# EEZ_DIB_DCP405_r2B11.net
KiCad netlist of a schematic drawn in EAGLE
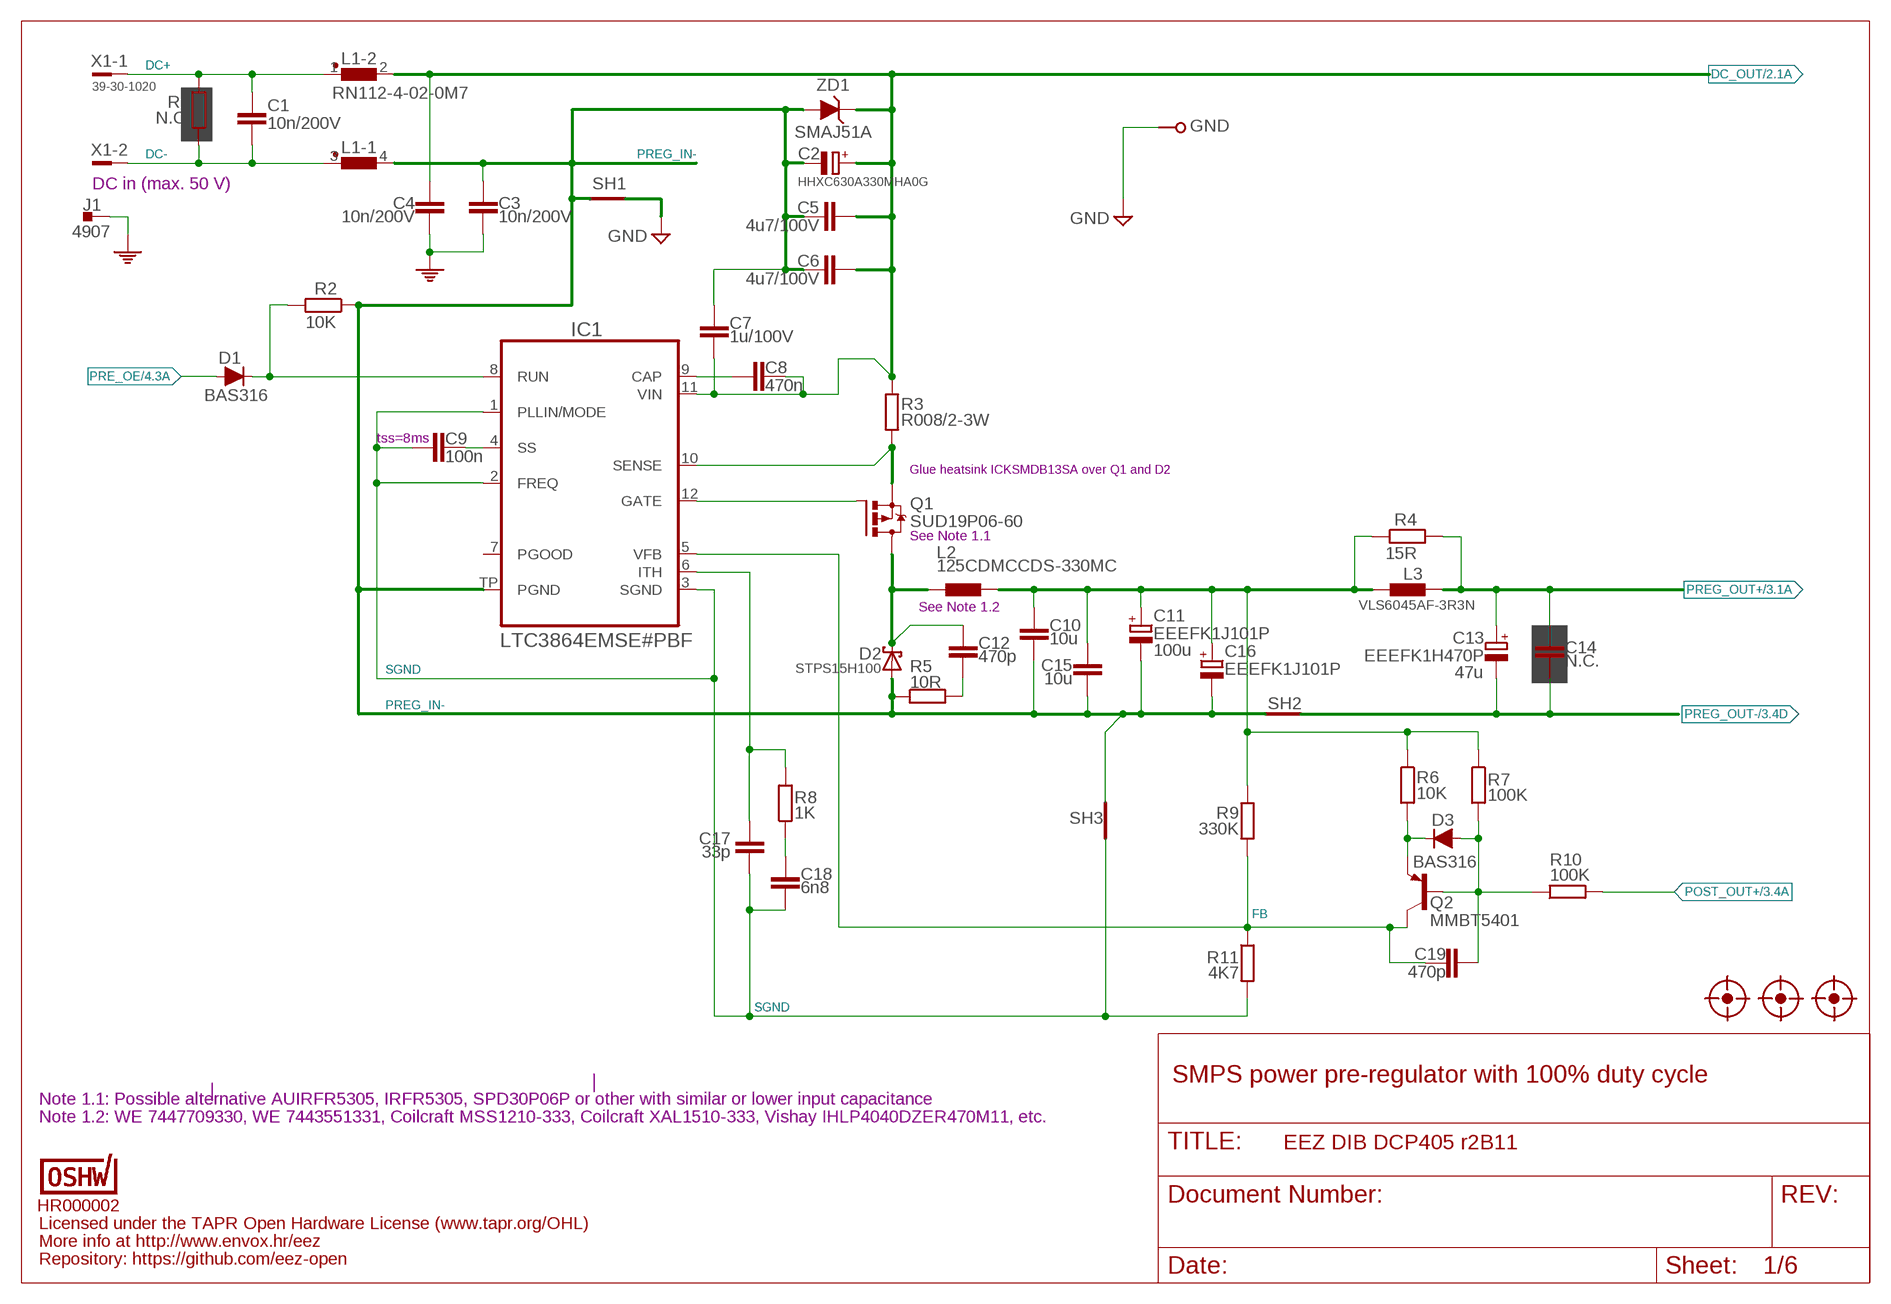
[diagram p0: schematic, sheet 1]
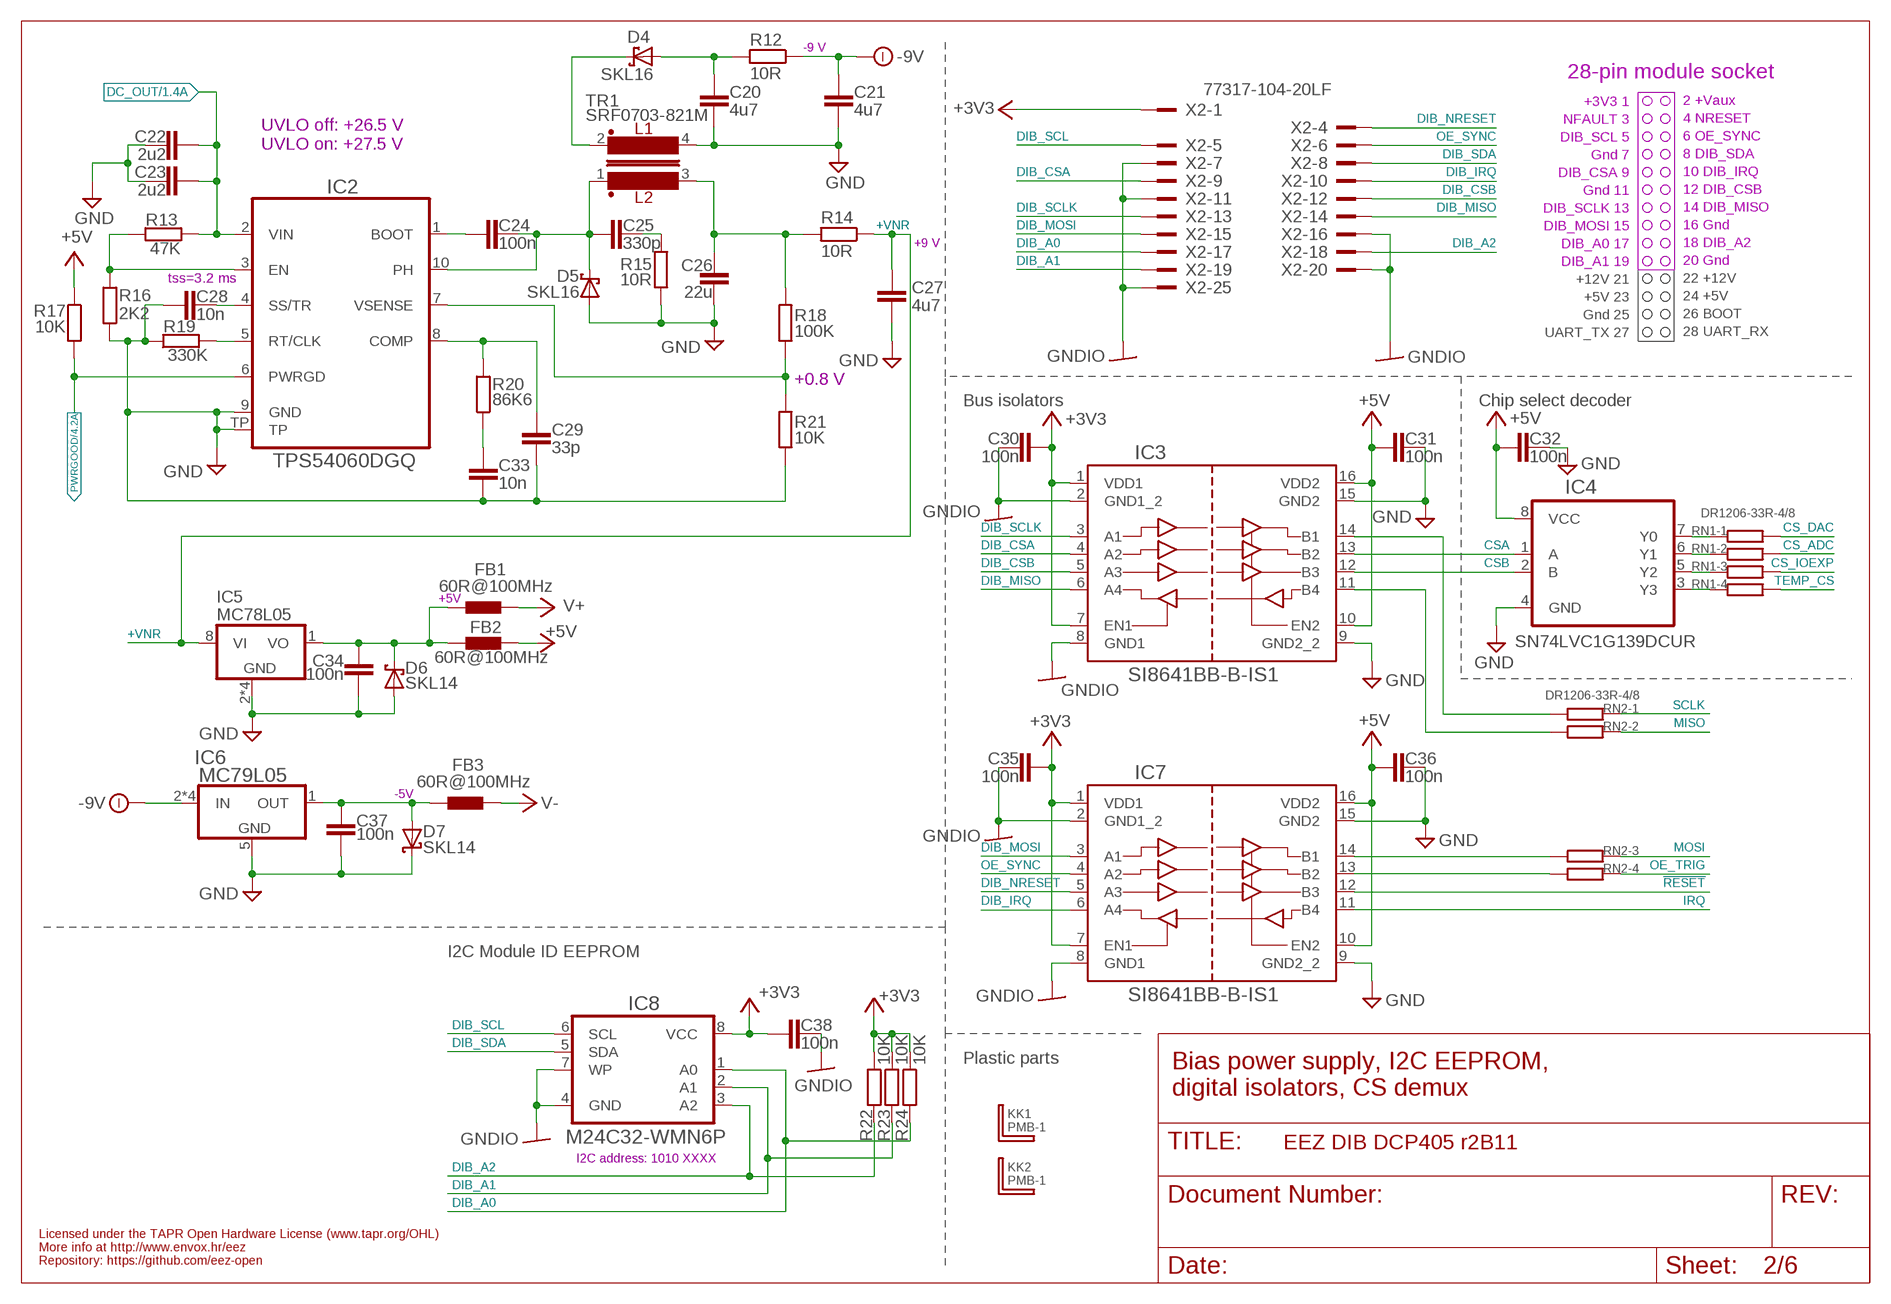
[diagram p1: schematic, sheet 2]
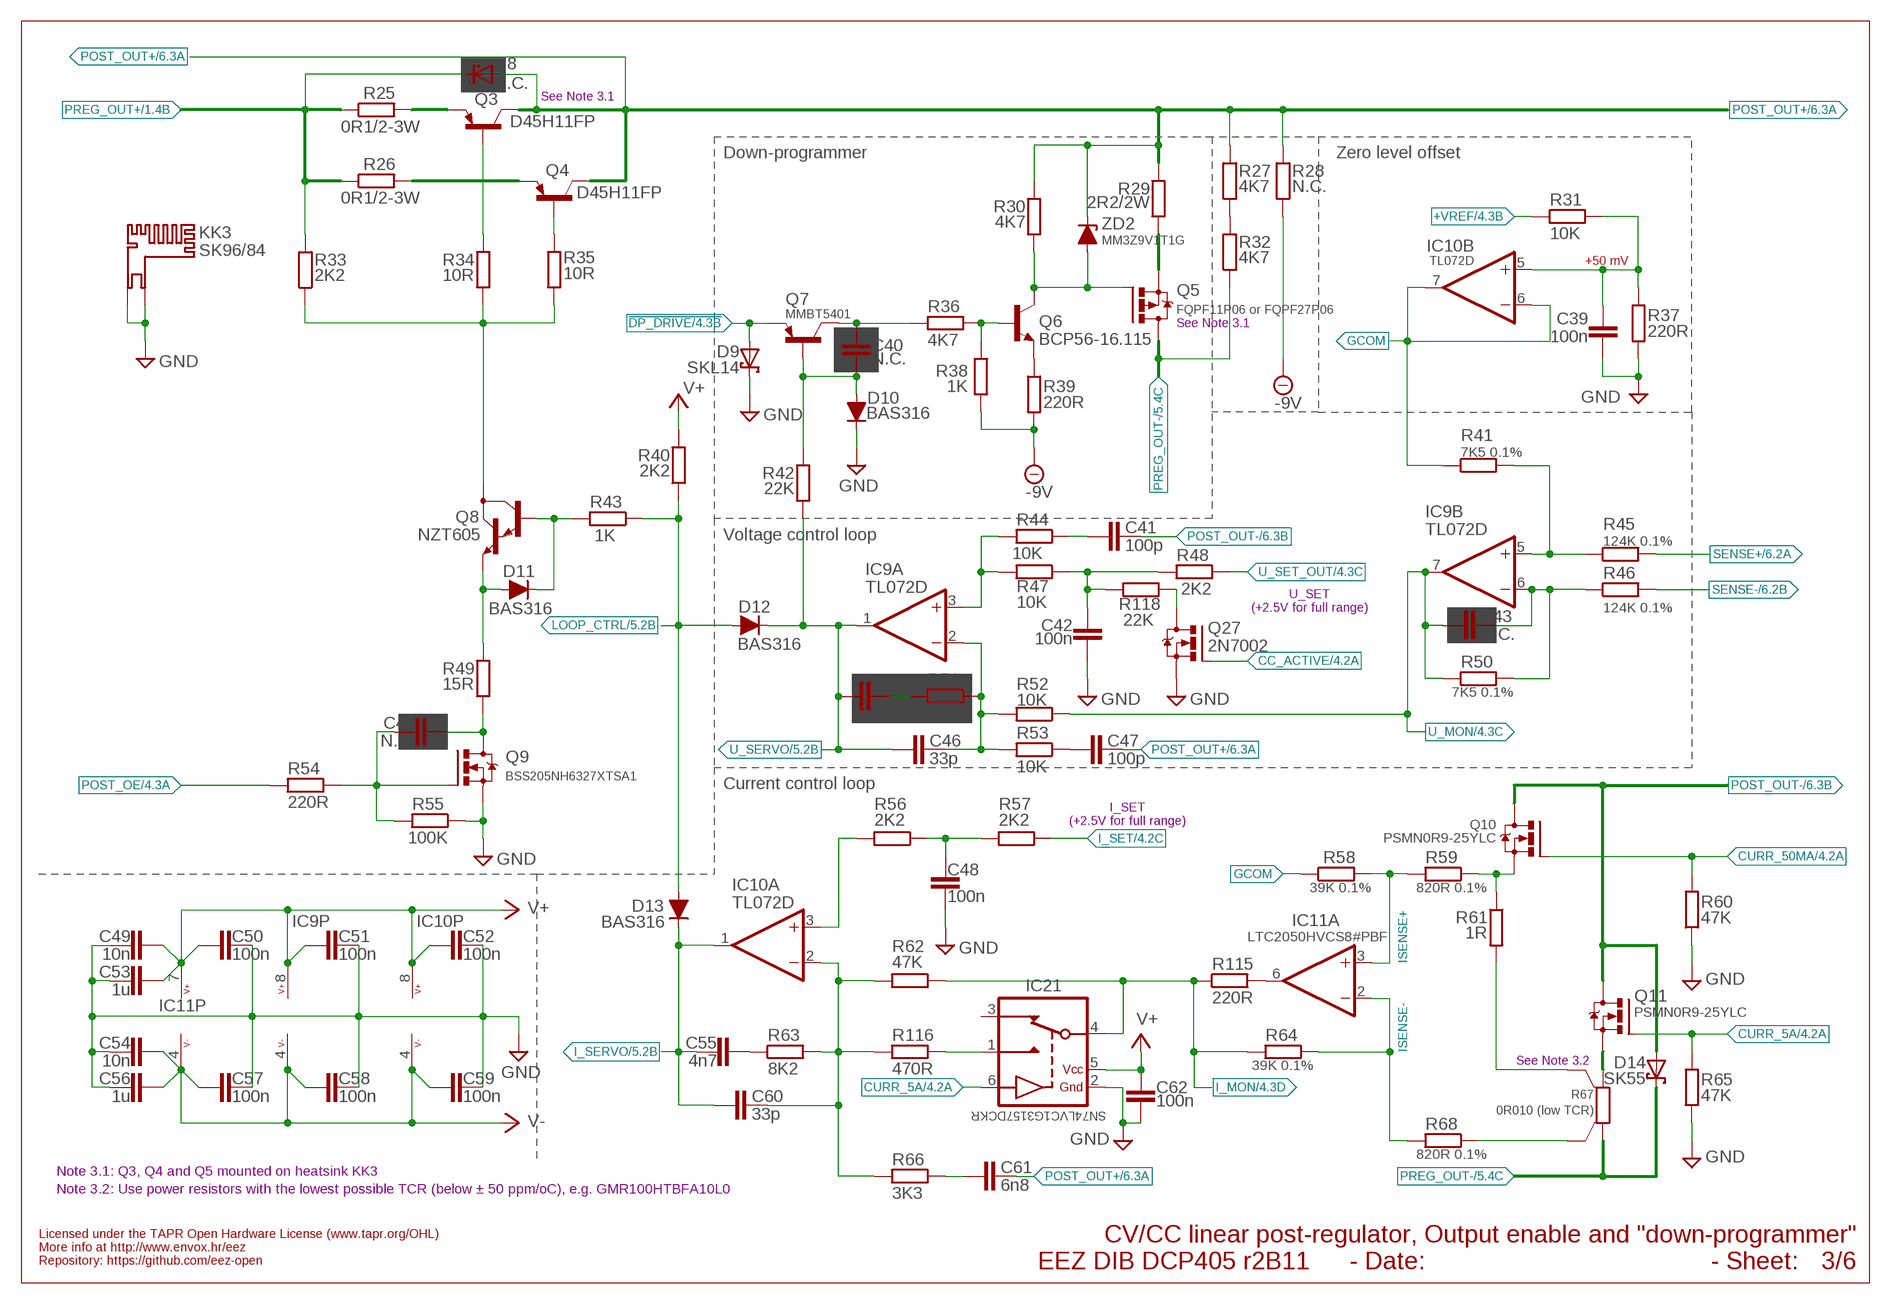
[diagram p2: schematic, sheet 3]
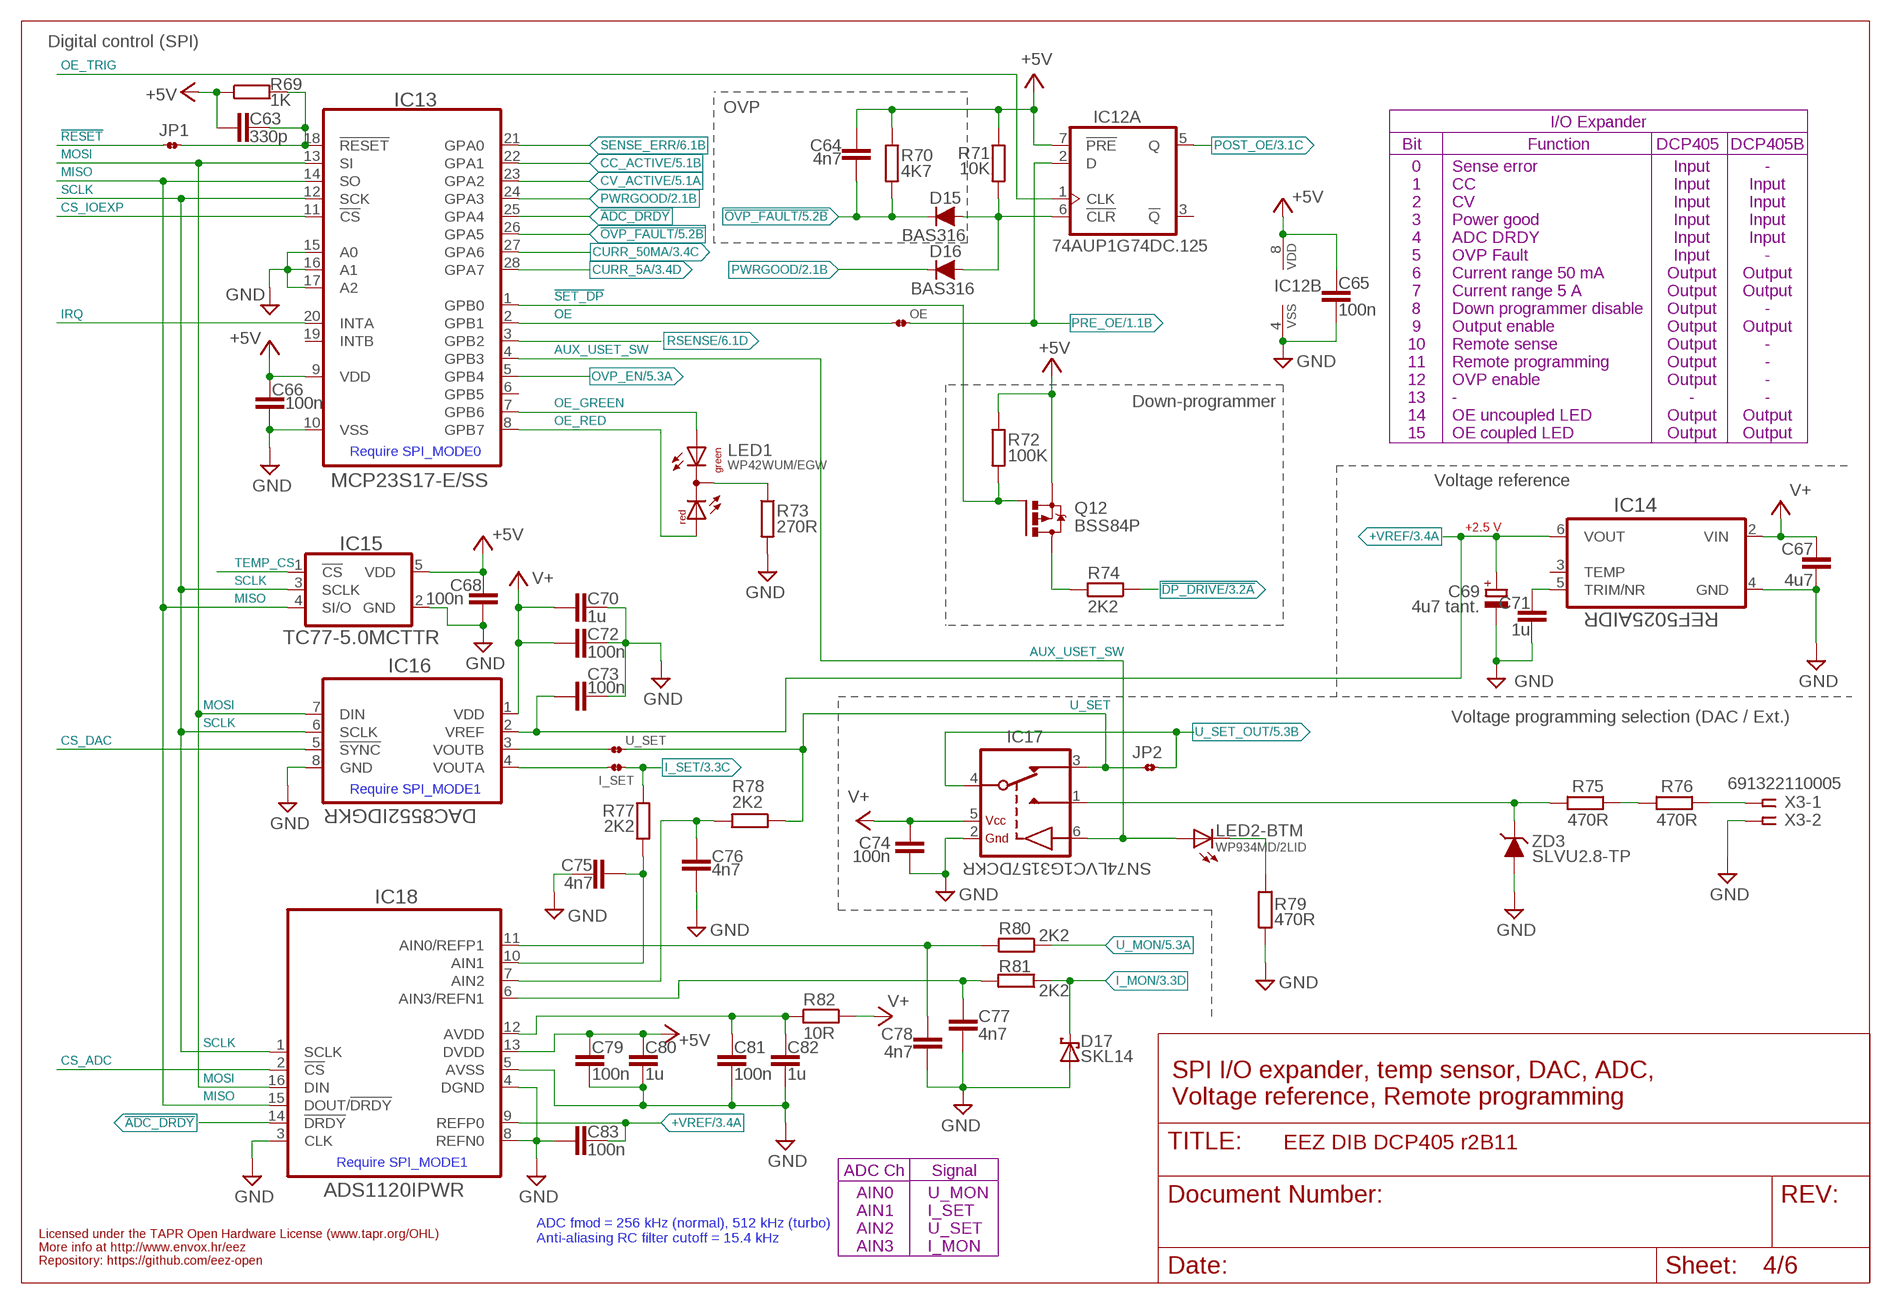
[diagram p3: schematic, sheet 4]
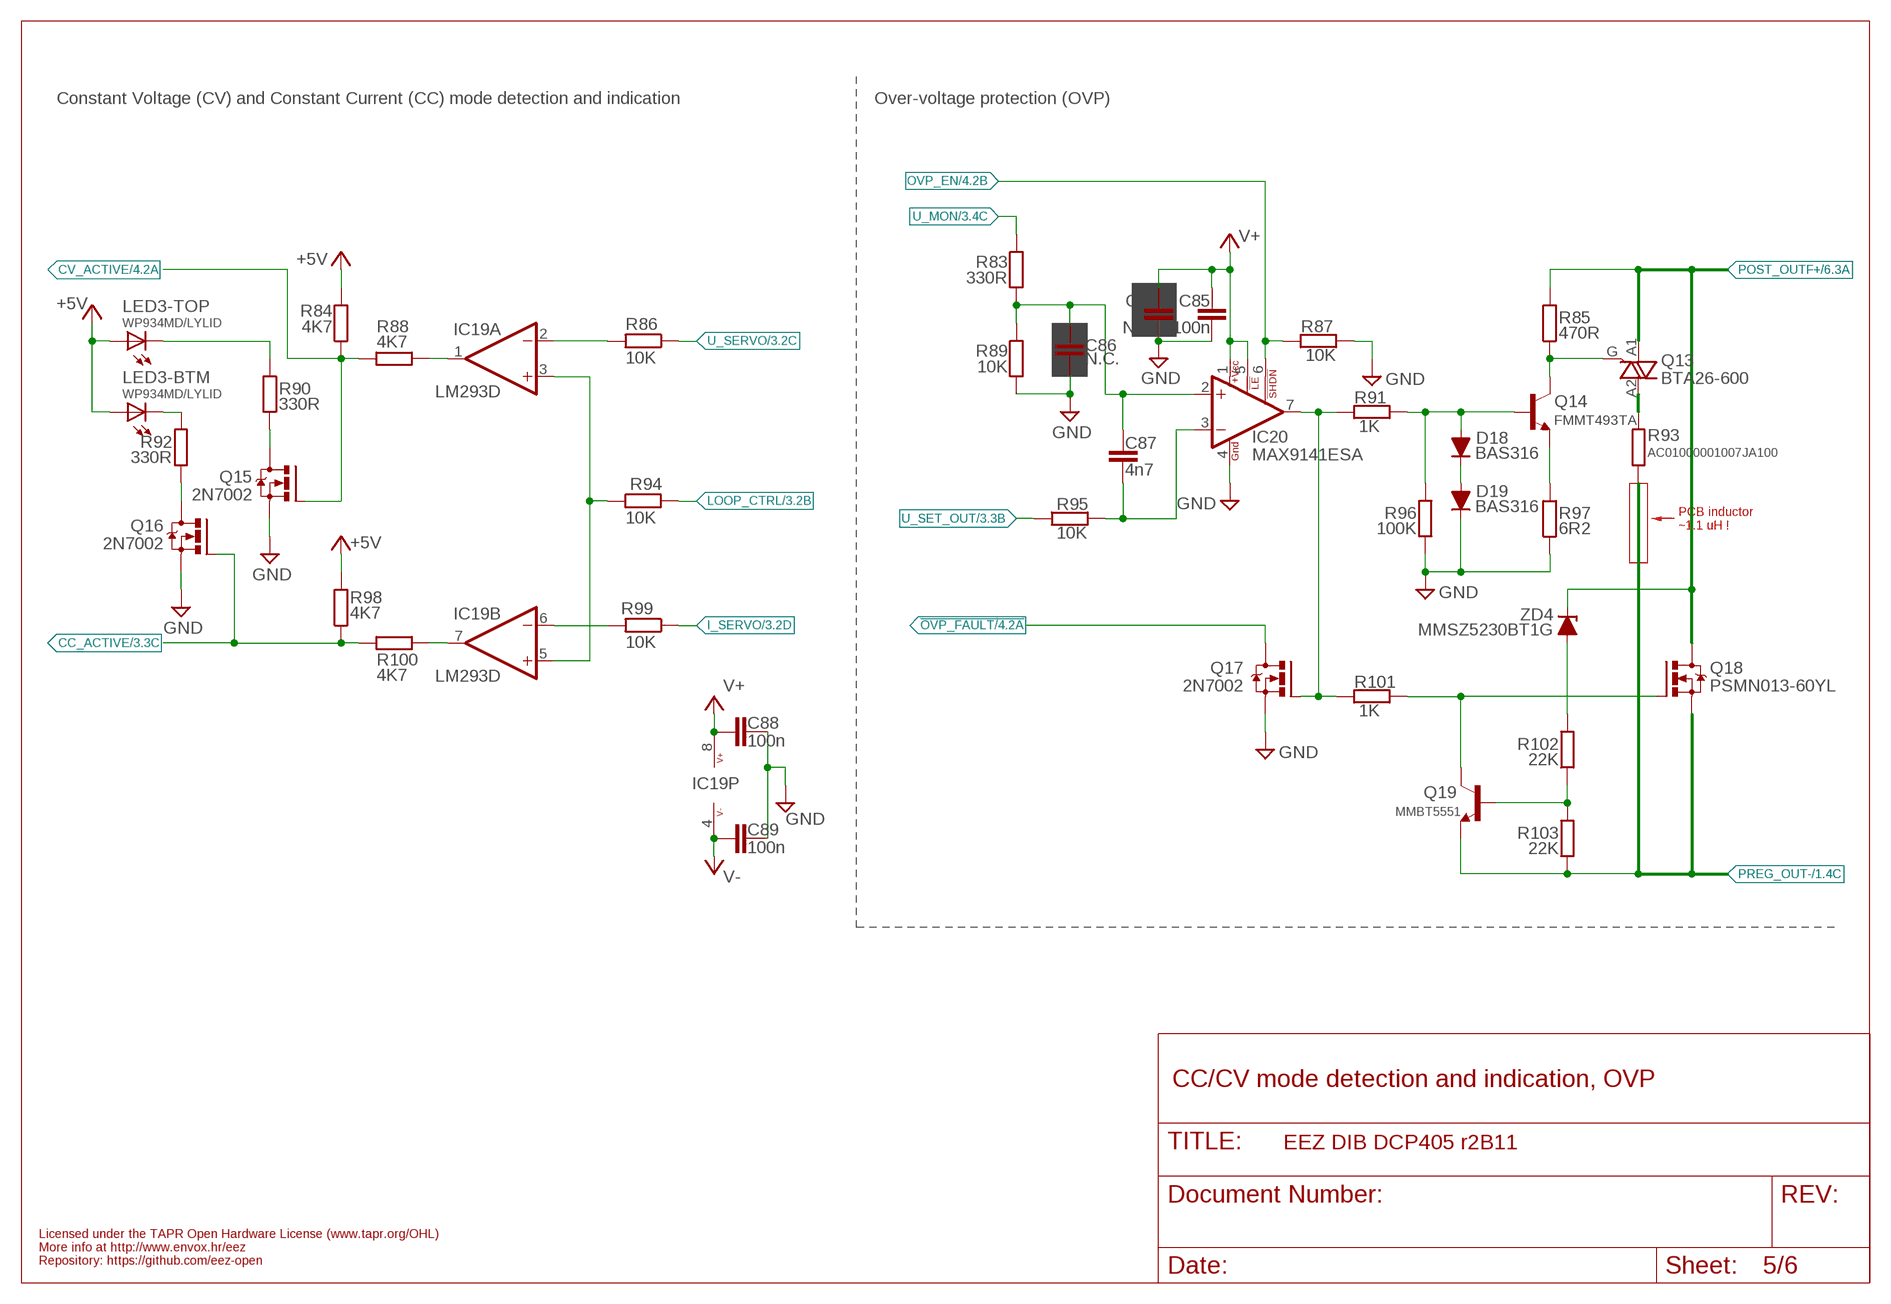
[diagram p4: schematic, sheet 5]
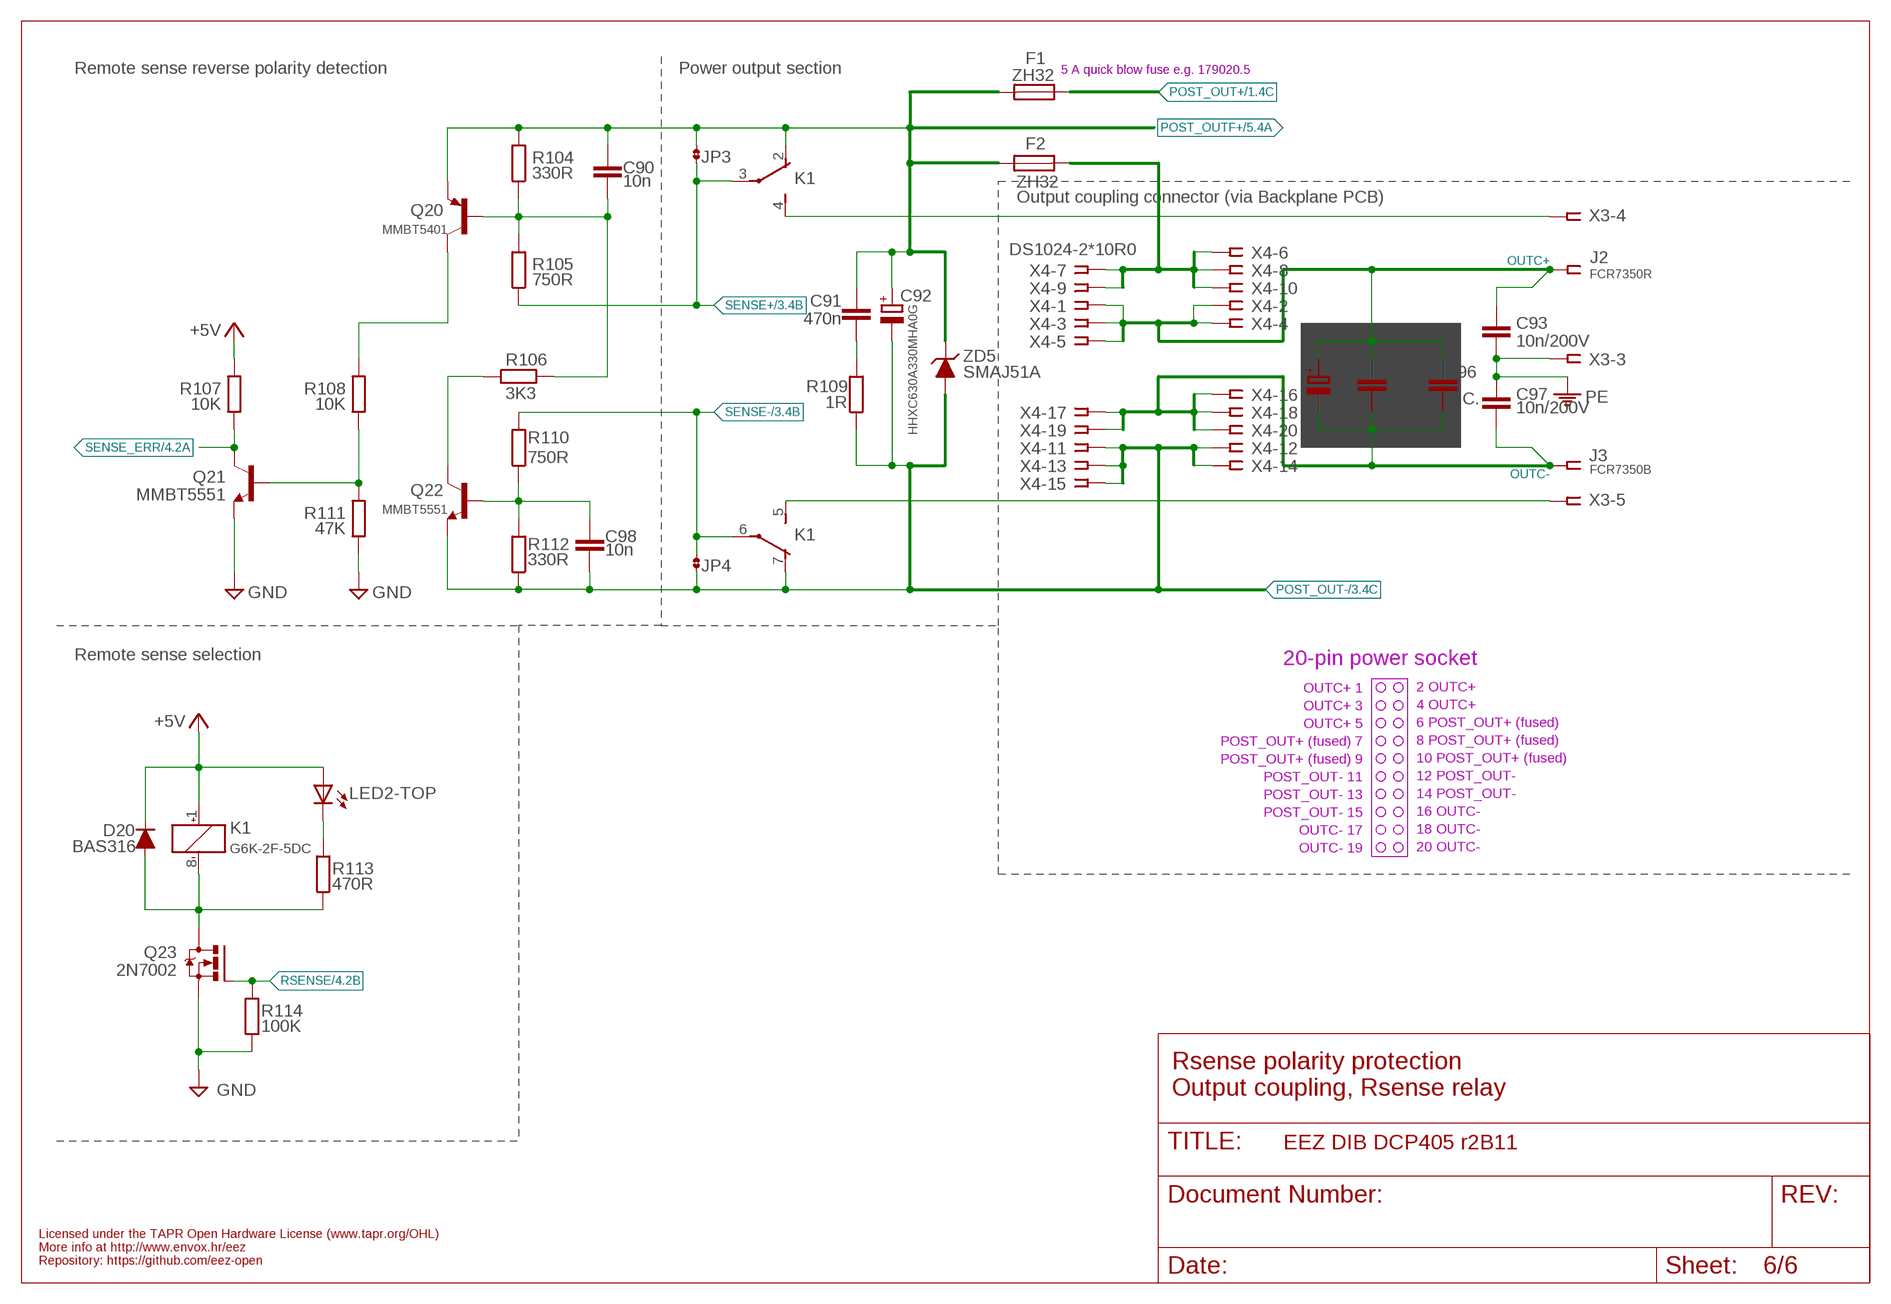
[diagram p5: schematic, sheet 6]

(export (version "E")
  (design (tool "Eeschema 10.0.6"))
  (components
    (comp (ref "C84")
      (value "N.C.")
      (footprint "eagle-import:C0805")
      (libsource (lib "eagle-import") (part "C-EUC0805"))
    )
    (comp (ref "C85")
      (value "100n")
      (footprint "eagle-import:C0603")
      (libsource (lib "eagle-import") (part "C-EUC0603"))
    )
    (comp (ref "C86")
      (value "N.C.")
      (footprint "eagle-import:C0805")
      (libsource (lib "eagle-import") (part "C-EUC0805"))
    )
    (comp (ref "C87")
      (value "4n7")
      (footprint "eagle-import:C0805")
      (libsource (lib "eagle-import") (part "C-EUC0805"))
    )
    (comp (ref "C88")
      (value "100n")
      (footprint "eagle-import:C0603")
      (libsource (lib "eagle-import") (part "C-EUC0603"))
    )
    (comp (ref "C89")
      (value "100n")
      (footprint "eagle-import:C0603")
      (libsource (lib "eagle-import") (part "C-EUC0603"))
    )
    (comp (ref "D18")
      (value "BAS316")
      (footprint "eagle-import:SOD323-R")
      (libsource (lib "eagle-import") (part "DIODESOD323R"))
    )
    (comp (ref "D19")
      (value "BAS316")
      (footprint "eagle-import:SOD323-R")
      (libsource (lib "eagle-import") (part "DIODESOD323R"))
    )
    (comp (ref "IC19")
      (value "LM293D")
      (footprint "eagle-import:SOIC127P600X173-8N")
      (libsource (lib "eagle-import") (part "LM293D"))
    )
    (comp (ref "IC20")
      (value "MAX9141ESA")
      (footprint "eagle-import:SOIC127P600X173-8N")
      (libsource (lib "eagle-import") (part "MAX9141ESA"))
    )
    (comp (ref "LED3")
      (value "WP934MD/LYLID")
      (footprint "eagle-import:WP934MD")
      (libsource (lib "eagle-import") (part "WP934MD/LYLID"))
    )
    (comp (ref "Q13")
      (value "BTA26-600")
      (footprint "eagle-import:TOP3_TRIAC_NOHOLE")
      (libsource (lib "eagle-import") (part "BTA41-2"))
    )
    (comp (ref "Q14")
      (value "FMMT493TA")
      (footprint "eagle-import:SOT23-BEC")
      (libsource (lib "eagle-import") (part "-NPN-SOT23-BECMMBT5551LT1"))
    )
    (comp (ref "Q15")
      (value "2N7002")
      (footprint "eagle-import:SOT103P240X110-3N")
      (fields (field (name "MPN") "2N7002-7-F"))
      (libsource (lib "eagle-import") (part "2N7002"))
    )
    (comp (ref "Q16")
      (value "2N7002")
      (footprint "eagle-import:SOT103P240X110-3N")
      (fields (field (name "MPN") "2N7002-7-F"))
      (libsource (lib "eagle-import") (part "2N7002"))
    )
    (comp (ref "Q17")
      (value "2N7002")
      (footprint "eagle-import:SOT103P240X110-3N")
      (fields
        (field (name "MPN") "2N7002-7-F")
        (field (name "MPN_1") "2N7002-7-F")
        (field (name "OC_FARNELL") "1713823")
        (field (name "OC_NEWARK") "25R5679")
        (field (name "PACKAGE") "SOT-23-3")
        (field (name "SUPPLIER") "DIODES INC.")
      )
      (libsource (lib "eagle-import") (part "2N7002"))
    )
    (comp (ref "Q18")
      (value "PSMN013-60YL")
      (footprint "eagle-import:SOT669")
      (libsource (lib "eagle-import") (part "N-MOSFETLFPAK"))
    )
    (comp (ref "Q19")
      (value "MMBT5551")
      (footprint "eagle-import:SOT23-BEC")
      (libsource (lib "eagle-import") (part "-NPN-SOT23-BECMMBT5551LT1"))
    )
    (comp (ref "R83")
      (value "330R")
      (footprint "eagle-import:R0805")
      (libsource (lib "eagle-import") (part "R-EU_R0805"))
    )
    (comp (ref "R84")
      (value "4K7")
      (footprint "eagle-import:R0805")
      (libsource (lib "eagle-import") (part "R-EU_R0805"))
    )
    (comp (ref "R85")
      (value "470R")
      (footprint "eagle-import:R0805")
      (libsource (lib "eagle-import") (part "R-EU_R0805"))
    )
    (comp (ref "R86")
      (value "10K")
      (footprint "eagle-import:R0805")
      (libsource (lib "eagle-import") (part "R-EU_R0805"))
    )
    (comp (ref "R87")
      (value "10K")
      (footprint "eagle-import:R0805")
      (libsource (lib "eagle-import") (part "R-EU_R0805"))
    )
    (comp (ref "R88")
      (value "4K7")
      (footprint "eagle-import:R0805")
      (libsource (lib "eagle-import") (part "R-EU_R0805"))
    )
    (comp (ref "R89")
      (value "10K")
      (footprint "eagle-import:R0805")
      (libsource (lib "eagle-import") (part "R-EU_R0805"))
    )
    (comp (ref "R90")
      (value "330R")
      (footprint "eagle-import:R0805")
      (libsource (lib "eagle-import") (part "R-EU_R0805"))
    )
    (comp (ref "R91")
      (value "1K")
      (footprint "eagle-import:R0805")
      (libsource (lib "eagle-import") (part "R-EU_R0805"))
    )
    (comp (ref "R92")
      (value "330R")
      (footprint "eagle-import:R0805")
      (libsource (lib "eagle-import") (part "R-EU_R0805"))
    )
    (comp (ref "R93")
      (value "AC01000001007JA100")
      (footprint "eagle-import:0411_15")
      (libsource (lib "eagle-import") (part "R-EU_0411/15"))
    )
    (comp (ref "R94")
      (value "10K")
      (footprint "eagle-import:R0805")
      (libsource (lib "eagle-import") (part "R-EU_R0805"))
    )
    (comp (ref "R95")
      (value "10K")
      (footprint "eagle-import:R0805")
      (libsource (lib "eagle-import") (part "R-EU_R0805"))
    )
    (comp (ref "R96")
      (value "100K")
      (footprint "eagle-import:R0805")
      (libsource (lib "eagle-import") (part "R-EU_R0805"))
    )
    (comp (ref "R97")
      (value "6R2")
      (footprint "eagle-import:R0805")
      (libsource (lib "eagle-import") (part "R-EU_R0805"))
    )
    (comp (ref "R98")
      (value "4K7")
      (footprint "eagle-import:R0805")
      (libsource (lib "eagle-import") (part "R-EU_R0805"))
    )
    (comp (ref "R99")
      (value "10K")
      (footprint "eagle-import:R0805")
      (libsource (lib "eagle-import") (part "R-EU_R0805"))
    )
    (comp (ref "R100")
      (value "4K7")
      (footprint "eagle-import:R0805")
      (libsource (lib "eagle-import") (part "R-EU_R0805"))
    )
    (comp (ref "R101")
      (value "1K")
      (footprint "eagle-import:R0805")
      (libsource (lib "eagle-import") (part "R-EU_R0805"))
    )
    (comp (ref "R102")
      (value "22K")
      (footprint "eagle-import:R0805")
      (libsource (lib "eagle-import") (part "R-EU_R0805"))
    )
    (comp (ref "R103")
      (value "22K")
      (footprint "eagle-import:R0805")
      (libsource (lib "eagle-import") (part "R-EU_R0805"))
    )
    (comp (ref "ZD4")
      (value "MMSZ5230BT1G")
      (footprint "eagle-import:SOD123")
      (libsource (lib "eagle-import") (part "ZENER-DIODESOD123"))
    )
    (comp (ref "C20")
      (value "4u7")
      (footprint "eagle-import:C1206")
      (libsource (lib "eagle-import") (part "C-EUC1206"))
    )
    (comp (ref "C21")
      (value "4u7")
      (footprint "eagle-import:C1206")
      (libsource (lib "eagle-import") (part "C-EUC1206"))
    )
    (comp (ref "C22")
      (value "2u2")
      (footprint "eagle-import:C1206")
      (libsource (lib "eagle-import") (part "C-EUC1206"))
    )
    (comp (ref "C23")
      (value "2u2")
      (footprint "eagle-import:C1206")
      (libsource (lib "eagle-import") (part "C-EUC1206"))
    )
    (comp (ref "C24")
      (value "100n")
      (footprint "eagle-import:C0603")
      (libsource (lib "eagle-import") (part "C-EUC0603"))
    )
    (comp (ref "C25")
      (value "330p")
      (footprint "eagle-import:C0805")
      (libsource (lib "eagle-import") (part "C-EUC0805"))
    )
    (comp (ref "C26")
      (value "22u")
      (footprint "eagle-import:C1210")
      (libsource (lib "eagle-import") (part "C-EUC1210"))
    )
    (comp (ref "C27")
      (value "4u7")
      (footprint "eagle-import:C1206")
      (libsource (lib "eagle-import") (part "C-EUC1206"))
    )
    (comp (ref "C28")
      (value "10n")
      (footprint "eagle-import:C0805")
      (libsource (lib "eagle-import") (part "C-EUC0805"))
    )
    (comp (ref "C29")
      (value "33p")
      (footprint "eagle-import:C0805")
      (libsource (lib "eagle-import") (part "C-EUC0805"))
    )
    (comp (ref "C30")
      (value "100n")
      (footprint "eagle-import:C0603")
      (libsource (lib "eagle-import") (part "C-EUC0603"))
    )
    (comp (ref "C31")
      (value "100n")
      (footprint "eagle-import:C0603")
      (libsource (lib "eagle-import") (part "C-EUC0603"))
    )
    (comp (ref "C32")
      (value "100n")
      (footprint "eagle-import:C0603")
      (libsource (lib "eagle-import") (part "C-EUC0603"))
    )
    (comp (ref "C33")
      (value "10n")
      (footprint "eagle-import:C0805")
      (libsource (lib "eagle-import") (part "C-EUC0805"))
    )
    (comp (ref "C34")
      (value "100n")
      (footprint "eagle-import:C0603")
      (libsource (lib "eagle-import") (part "C-EUC0603"))
    )
    (comp (ref "C35")
      (value "100n")
      (footprint "eagle-import:C0603")
      (libsource (lib "eagle-import") (part "C-EUC0603"))
    )
    (comp (ref "C36")
      (value "100n")
      (footprint "eagle-import:C0603")
      (libsource (lib "eagle-import") (part "C-EUC0603"))
    )
    (comp (ref "C37")
      (value "100n")
      (footprint "eagle-import:C0603")
      (libsource (lib "eagle-import") (part "C-EUC0603"))
    )
    (comp (ref "C38")
      (value "100n")
      (footprint "eagle-import:C0603")
      (libsource (lib "eagle-import") (part "C-EUC0603"))
    )
    (comp (ref "D4")
      (value "SKL16")
      (footprint "eagle-import:SOD123")
      (libsource (lib "eagle-import") (part "SCHOTTKYSOD123"))
    )
    (comp (ref "D5")
      (value "SKL16")
      (footprint "eagle-import:SOD123")
      (libsource (lib "eagle-import") (part "SCHOTTKYSOD123"))
    )
    (comp (ref "D6")
      (value "SKL14")
      (footprint "eagle-import:SOD123")
      (libsource (lib "eagle-import") (part "SCHOTTKYSOD123"))
    )
    (comp (ref "D7")
      (value "SKL14")
      (footprint "eagle-import:SOD123")
      (libsource (lib "eagle-import") (part "SCHOTTKYSOD123"))
    )
    (comp (ref "FB1")
      (value "60R@100MHz")
      (footprint "eagle-import:BEAD0603")
      (libsource (lib "eagle-import") (part "FERRITE_BEAD0603"))
    )
    (comp (ref "FB2")
      (value "60R@100MHz")
      (footprint "eagle-import:BEAD0603")
      (libsource (lib "eagle-import") (part "FERRITE_BEAD0603"))
    )
    (comp (ref "FB3")
      (value "60R@100MHz")
      (footprint "eagle-import:BEAD0603")
      (libsource (lib "eagle-import") (part "FERRITE_BEAD0603"))
    )
    (comp (ref "IC2")
      (value "TPS54060DGQ")
      (footprint "eagle-import:SOP50P490X110-11N")
      (fields (field (name "MPN") "TPS54060ADGQ"))
      (libsource (lib "eagle-import") (part "TPS54060DGQ"))
    )
    (comp (ref "IC3")
      (value "SI8641BB-B-IS1")
      (footprint "eagle-import:SOIC-16")
      (libsource (lib "eagle-import") (part "SI8641NSOIC-16"))
    )
    (comp (ref "IC4")
      (value "SN74LVC1G139DCUR")
      (footprint "eagle-import:DCU8")
      (libsource (lib "eagle-import") (part "SN74LVC1G139-VSSOP"))
    )
    (comp (ref "IC5")
      (value "MC78L05")
      (footprint "eagle-import:SOIC127P600X173-8N")
      (libsource (lib "eagle-import") (part "MC78LXXSOIC8"))
    )
    (comp (ref "IC6")
      (value "MC79L05")
      (footprint "eagle-import:SOIC127P600X173-8N")
      (libsource (lib "eagle-import") (part "MC79LXXSOIC"))
    )
    (comp (ref "IC7")
      (value "SI8641BB-B-IS1")
      (footprint "eagle-import:SOIC-16")
      (libsource (lib "eagle-import") (part "SI8641NSOIC-16"))
    )
    (comp (ref "IC8")
      (value "M24C32-WMN6P")
      (footprint "eagle-import:SOIC127P600X173-8N")
      (libsource (lib "eagle-import") (part "AT24CXXSOIC8"))
    )
    (comp (ref "KK1")
      (value "PMB-1")
      (footprint "eagle-import:PCB-MB")
      (libsource (lib "eagle-import") (part "PCB-MB"))
    )
    (comp (ref "KK2")
      (value "PMB-1")
      (footprint "eagle-import:PCB-MB")
      (libsource (lib "eagle-import") (part "PCB-MB"))
    )
    (comp (ref "R12")
      (value "10R")
      (footprint "eagle-import:R1206")
      (libsource (lib "eagle-import") (part "R-EU_R1206"))
    )
    (comp (ref "R13")
      (value "47K")
      (footprint "eagle-import:R0805")
      (libsource (lib "eagle-import") (part "R-EU_R0805"))
    )
    (comp (ref "R14")
      (value "10R")
      (footprint "eagle-import:R1206")
      (libsource (lib "eagle-import") (part "R-EU_R1206"))
    )
    (comp (ref "R15")
      (value "10R")
      (footprint "eagle-import:R1206")
      (libsource (lib "eagle-import") (part "R-EU_R1206"))
    )
    (comp (ref "R16")
      (value "2K2")
      (footprint "eagle-import:R0805")
      (libsource (lib "eagle-import") (part "R-EU_R0805"))
    )
    (comp (ref "R17")
      (value "10K")
      (footprint "eagle-import:R0805")
      (libsource (lib "eagle-import") (part "R-EU_R0805"))
    )
    (comp (ref "R18")
      (value "100K")
      (footprint "eagle-import:R0805")
      (libsource (lib "eagle-import") (part "R-EU_R0805"))
    )
    (comp (ref "R19")
      (value "330K")
      (footprint "eagle-import:R0805")
      (libsource (lib "eagle-import") (part "R-EU_R0805"))
    )
    (comp (ref "R20")
      (value "86K6")
      (footprint "eagle-import:R0805")
      (libsource (lib "eagle-import") (part "R-EU_R0805"))
    )
    (comp (ref "R21")
      (value "10K")
      (footprint "eagle-import:R0805")
      (libsource (lib "eagle-import") (part "R-EU_R0805"))
    )
    (comp (ref "R22")
      (value "10K")
      (footprint "eagle-import:R0805")
      (libsource (lib "eagle-import") (part "R-EU_R0805"))
    )
    (comp (ref "R23")
      (value "10K")
      (footprint "eagle-import:R0805")
      (libsource (lib "eagle-import") (part "R-EU_R0805"))
    )
    (comp (ref "R24")
      (value "10K")
      (footprint "eagle-import:R0805")
      (libsource (lib "eagle-import") (part "R-EU_R0805"))
    )
    (comp (ref "RN1")
      (value "DR1206-33R-4/8")
      (footprint "eagle-import:CAY16")
      (libsource (lib "eagle-import") (part "R_ARRAY4"))
    )
    (comp (ref "RN2")
      (value "DR1206-33R-4/8")
      (footprint "eagle-import:CAY16")
      (libsource (lib "eagle-import") (part "R_ARRAY4"))
    )
    (comp (ref "TR1")
      (value "SRF0703-821M")
      (footprint "eagle-import:SRF0703")
      (libsource (lib "eagle-import") (part "BOURNS_SRF0703INV"))
    )
    (comp (ref "X2")
      (value "77317-104-20LF")
      (footprint "eagle-import:77317-104-28LF")
      (libsource (lib "eagle-import") (part "77317-104-28LF"))
    )
    (comp (ref "C39")
      (value "100n")
      (footprint "eagle-import:C0603")
      (libsource (lib "eagle-import") (part "C-EUC0603"))
    )
    (comp (ref "C40")
      (value "N.C.")
      (footprint "eagle-import:C0805")
      (libsource (lib "eagle-import") (part "C-EUC0805"))
    )
    (comp (ref "C41")
      (value "100p")
      (footprint "eagle-import:C0805")
      (libsource (lib "eagle-import") (part "C-EUC0805"))
    )
    (comp (ref "C42")
      (value "100n")
      (footprint "eagle-import:C0603")
      (libsource (lib "eagle-import") (part "C-EUC0603"))
    )
    (comp (ref "C43")
      (value "N.C.")
      (footprint "eagle-import:C0805")
      (libsource (lib "eagle-import") (part "C-EUC0805"))
    )
    (comp (ref "C44")
      (value "N.C.")
      (footprint "eagle-import:C0805")
      (libsource (lib "eagle-import") (part "C-EUC0805"))
    )
    (comp (ref "C45")
      (value "N.C.")
      (footprint "eagle-import:C0805")
      (libsource (lib "eagle-import") (part "C-EUC0805"))
    )
    (comp (ref "C46")
      (value "33p")
      (footprint "eagle-import:C0805")
      (libsource (lib "eagle-import") (part "C-EUC0805"))
    )
    (comp (ref "C47")
      (value "100p")
      (footprint "eagle-import:C0805")
      (libsource (lib "eagle-import") (part "C-EUC0805"))
    )
    (comp (ref "C48")
      (value "100n")
      (footprint "eagle-import:C0603")
      (libsource (lib "eagle-import") (part "C-EUC0603"))
    )
    (comp (ref "C49")
      (value "10n")
      (footprint "eagle-import:C0805")
      (libsource (lib "eagle-import") (part "C-EUC0805"))
    )
    (comp (ref "C50")
      (value "100n")
      (footprint "eagle-import:C0603")
      (libsource (lib "eagle-import") (part "C-EUC0603"))
    )
    (comp (ref "C51")
      (value "100n")
      (footprint "eagle-import:C0603")
      (libsource (lib "eagle-import") (part "C-EUC0603"))
    )
    (comp (ref "C52")
      (value "100n")
      (footprint "eagle-import:C0603")
      (libsource (lib "eagle-import") (part "C-EUC0603"))
    )
    (comp (ref "C53")
      (value "1u")
      (footprint "eagle-import:C0805")
      (libsource (lib "eagle-import") (part "C-EUC0805"))
    )
    (comp (ref "C54")
      (value "10n")
      (footprint "eagle-import:C0805")
      (libsource (lib "eagle-import") (part "C-EUC0805"))
    )
    (comp (ref "C55")
      (value "4n7")
      (footprint "eagle-import:C0805")
      (libsource (lib "eagle-import") (part "C-EUC0805"))
    )
    (comp (ref "C56")
      (value "1u")
      (footprint "eagle-import:C0805")
      (libsource (lib "eagle-import") (part "C-EUC0805"))
    )
    (comp (ref "C57")
      (value "100n")
      (footprint "eagle-import:C0603")
      (libsource (lib "eagle-import") (part "C-EUC0603"))
    )
    (comp (ref "C58")
      (value "100n")
      (footprint "eagle-import:C0603")
      (libsource (lib "eagle-import") (part "C-EUC0603"))
    )
    (comp (ref "C59")
      (value "100n")
      (footprint "eagle-import:C0603")
      (libsource (lib "eagle-import") (part "C-EUC0603"))
    )
    (comp (ref "C60")
      (value "33p")
      (footprint "eagle-import:C0805")
      (libsource (lib "eagle-import") (part "C-EUC0805"))
    )
    (comp (ref "C61")
      (value "6n8")
      (footprint "eagle-import:C0805")
      (libsource (lib "eagle-import") (part "C-EUC0805"))
    )
    (comp (ref "C62")
      (value "100n")
      (footprint "eagle-import:C0603")
      (libsource (lib "eagle-import") (part "C-EUC0603"))
    )
    (comp (ref "D8")
      (value "N.C.")
      (footprint "eagle-import:SOD123")
      (libsource (lib "eagle-import") (part "SCHOTTKYSOD123"))
    )
    (comp (ref "D9")
      (value "SKL14")
      (footprint "eagle-import:SOD123")
      (libsource (lib "eagle-import") (part "SCHOTTKYSOD123"))
    )
    (comp (ref "D10")
      (value "BAS316")
      (footprint "eagle-import:SOD323-R")
      (libsource (lib "eagle-import") (part "DIODESOD323R"))
    )
    (comp (ref "D11")
      (value "BAS316")
      (footprint "eagle-import:SOD323-R")
      (libsource (lib "eagle-import") (part "DIODESOD323R"))
    )
    (comp (ref "D12")
      (value "BAS316")
      (footprint "eagle-import:SOD323-R")
      (libsource (lib "eagle-import") (part "DIODESOD323R"))
    )
    (comp (ref "D13")
      (value "BAS316")
      (footprint "eagle-import:SOD323-R")
      (libsource (lib "eagle-import") (part "DIODESOD323R"))
    )
    (comp (ref "D14")
      (value "SK55")
      (footprint "eagle-import:SMB")
      (libsource (lib "eagle-import") (part "SCHOTTKYSMB"))
    )
    (comp (ref "IC9")
      (value "TL072D")
      (footprint "eagle-import:SOIC127P600X173-8N")
      (libsource (lib "eagle-import") (part "TL072SOIC8"))
    )
    (comp (ref "IC10")
      (value "TL072D")
      (footprint "eagle-import:SOIC127P600X173-8N")
      (libsource (lib "eagle-import") (part "TL072SOIC8"))
    )
    (comp (ref "IC11")
      (value "LTC2050HVCS8#PBF")
      (footprint "eagle-import:SOIC127P600X173-8N")
      (libsource (lib "eagle-import") (part "OP27GSZSO8"))
    )
    (comp (ref "IC21")
      (value "SN74LVC1G3157DCKR")
      (footprint "eagle-import:SOT65P210X110-6N")
      (libsource (lib "eagle-import") (part "SN74LVC1G3157-DCK"))
    )
    (comp (ref "KK3")
      (value "SK96/84")
      (footprint "eagle-import:SK96_84")
      (libsource (lib "eagle-import") (part "SK96/84"))
    )
    (comp (ref "Q3")
      (value "D45H11FP")
      (footprint "eagle-import:TO220FP-V")
      (libsource (lib "eagle-import") (part "D45H11-FPV"))
    )
    (comp (ref "Q4")
      (value "D45H11FP")
      (footprint "eagle-import:TO220FP-V")
      (libsource (lib "eagle-import") (part "D45H11-FPV"))
    )
    (comp (ref "Q5")
      (value "FQPF11P06 or FQPF27P06")
      (footprint "eagle-import:TO220FP-V")
      (libsource (lib "eagle-import") (part "P-MOSFET-FPV"))
    )
    (comp (ref "Q6")
      (value "BCP56-16.115")
      (footprint "eagle-import:SOT230P700X180-4N")
      (libsource (lib "eagle-import") (part "BCP56"))
    )
    (comp (ref "Q7")
      (value "MMBT5401")
      (footprint "eagle-import:SOT23-BEC")
      (libsource (lib "eagle-import") (part "-PNP-SOT23-BECBC857B"))
    )
    (comp (ref "Q8")
      (value "NZT605")
      (footprint "eagle-import:SOT230P700X180-4N")
      (libsource (lib "eagle-import") (part "NZT605"))
    )
    (comp (ref "Q9")
      (value "BSS205NH6327XTSA1")
      (footprint "eagle-import:SOT103P240X110-3N")
      (fields
        (field (name "MPN") "2N7002-7-F")
        (field (name "MPN_1") "2N7002-7-F")
        (field (name "OC_FARNELL") "1713823")
        (field (name "OC_NEWARK") "25R5679")
        (field (name "PACKAGE") "SOT-23-3")
        (field (name "SUPPLIER") "DIODES INC.")
      )
      (libsource (lib "eagle-import") (part "2N7002"))
    )
    (comp (ref "Q10")
      (value "PSMN0R9-25YLC")
      (footprint "eagle-import:SOT669")
      (libsource (lib "eagle-import") (part "N-MOSFETLFPAK"))
    )
    (comp (ref "Q11")
      (value "PSMN0R9-25YLC")
      (footprint "eagle-import:SOT669")
      (libsource (lib "eagle-import") (part "N-MOSFETLFPAK"))
    )
    (comp (ref "Q27")
      (value "2N7002")
      (footprint "eagle-import:SOT103P240X110-3N")
      (fields (field (name "MPN") "2N7002-7-F"))
      (libsource (lib "eagle-import") (part "2N7002"))
    )
    (comp (ref "R25")
      (value "0R1/2-3W")
      (footprint "eagle-import:R2512")
      (libsource (lib "eagle-import") (part "R-EU_R2512"))
    )
    (comp (ref "R26")
      (value "0R1/2-3W")
      (footprint "eagle-import:R2512")
      (libsource (lib "eagle-import") (part "R-EU_R2512"))
    )
    (comp (ref "R27")
      (value "4K7")
      (footprint "eagle-import:R0805")
      (libsource (lib "eagle-import") (part "R-EU_R0805"))
    )
    (comp (ref "R28")
      (value "N.C.")
      (footprint "eagle-import:R0805")
      (libsource (lib "eagle-import") (part "R-EU_R0805"))
    )
    (comp (ref "R29")
      (value "2R2/2W")
      (footprint "eagle-import:R2512")
      (libsource (lib "eagle-import") (part "R-EU_R2512"))
    )
    (comp (ref "R30")
      (value "4K7")
      (footprint "eagle-import:R0805")
      (libsource (lib "eagle-import") (part "R-EU_R0805"))
    )
    (comp (ref "R31")
      (value "10K")
      (footprint "eagle-import:R0805")
      (libsource (lib "eagle-import") (part "R-EU_R0805"))
    )
    (comp (ref "R32")
      (value "4K7")
      (footprint "eagle-import:R0805")
      (libsource (lib "eagle-import") (part "R-EU_R0805"))
    )
    (comp (ref "R33")
      (value "2K2")
      (footprint "eagle-import:R0805")
      (libsource (lib "eagle-import") (part "R-EU_R0805"))
    )
    (comp (ref "R34")
      (value "10R")
      (footprint "eagle-import:R1206")
      (libsource (lib "eagle-import") (part "R-EU_R1206"))
    )
    (comp (ref "R35")
      (value "10R")
      (footprint "eagle-import:R1206")
      (libsource (lib "eagle-import") (part "R-EU_R1206"))
    )
    (comp (ref "R36")
      (value "4K7")
      (footprint "eagle-import:R0805")
      (libsource (lib "eagle-import") (part "R-EU_R0805"))
    )
    (comp (ref "R37")
      (value "220R")
      (footprint "eagle-import:R0805")
      (libsource (lib "eagle-import") (part "R-EU_R0805"))
    )
    (comp (ref "R38")
      (value "1K")
      (footprint "eagle-import:R0805")
      (libsource (lib "eagle-import") (part "R-EU_R0805"))
    )
    (comp (ref "R39")
      (value "220R")
      (footprint "eagle-import:R0805")
      (libsource (lib "eagle-import") (part "R-EU_R0805"))
    )
    (comp (ref "R40")
      (value "2K2")
      (footprint "eagle-import:R0805")
      (libsource (lib "eagle-import") (part "R-EU_R0805"))
    )
    (comp (ref "R41")
      (value "7K5 0.1%")
      (footprint "eagle-import:R0805")
      (libsource (lib "eagle-import") (part "R-EU_R0805"))
    )
    (comp (ref "R42")
      (value "22K")
      (footprint "eagle-import:R0805")
      (libsource (lib "eagle-import") (part "R-EU_R0805"))
    )
    (comp (ref "R43")
      (value "1K")
      (footprint "eagle-import:R0805")
      (libsource (lib "eagle-import") (part "R-EU_R0805"))
    )
    (comp (ref "R44")
      (value "10K")
      (footprint "eagle-import:R0805")
      (libsource (lib "eagle-import") (part "R-EU_R0805"))
    )
    (comp (ref "R45")
      (value "124K 0.1%")
      (footprint "eagle-import:R0805")
      (libsource (lib "eagle-import") (part "R-EU_R0805"))
    )
    (comp (ref "R46")
      (value "124K 0.1%")
      (footprint "eagle-import:R0805")
      (libsource (lib "eagle-import") (part "R-EU_R0805"))
    )
    (comp (ref "R47")
      (value "10K")
      (footprint "eagle-import:R0805")
      (libsource (lib "eagle-import") (part "R-EU_R0805"))
    )
    (comp (ref "R48")
      (value "2K2")
      (footprint "eagle-import:R0805")
      (libsource (lib "eagle-import") (part "R-EU_R0805"))
    )
    (comp (ref "R49")
      (value "15R")
      (footprint "eagle-import:R2010")
      (libsource (lib "eagle-import") (part "R-EU_R2010"))
    )
    (comp (ref "R50")
      (value "7K5 0.1%")
      (footprint "eagle-import:R0805")
      (libsource (lib "eagle-import") (part "R-EU_R0805"))
    )
    (comp (ref "R51")
      (value "N.C.")
      (footprint "eagle-import:R0805")
      (libsource (lib "eagle-import") (part "R-EU_R0805"))
    )
    (comp (ref "R52")
      (value "10K")
      (footprint "eagle-import:R0805")
      (libsource (lib "eagle-import") (part "R-EU_R0805"))
    )
    (comp (ref "R53")
      (value "10K")
      (footprint "eagle-import:R0805")
      (libsource (lib "eagle-import") (part "R-EU_R0805"))
    )
    (comp (ref "R54")
      (value "220R")
      (footprint "eagle-import:R0805")
      (libsource (lib "eagle-import") (part "R-EU_R0805"))
    )
    (comp (ref "R55")
      (value "100K")
      (footprint "eagle-import:R0805")
      (libsource (lib "eagle-import") (part "R-EU_R0805"))
    )
    (comp (ref "R56")
      (value "2K2")
      (footprint "eagle-import:R0805")
      (libsource (lib "eagle-import") (part "R-EU_R0805"))
    )
    (comp (ref "R57")
      (value "2K2")
      (footprint "eagle-import:R0805")
      (libsource (lib "eagle-import") (part "R-EU_R0805"))
    )
    (comp (ref "R58")
      (value "39K 0.1%")
      (footprint "eagle-import:R0805")
      (libsource (lib "eagle-import") (part "R-EU_R0805"))
    )
    (comp (ref "R59")
      (value "820R 0.1%")
      (footprint "eagle-import:R0805")
      (libsource (lib "eagle-import") (part "R-EU_R0805"))
    )
    (comp (ref "R60")
      (value "47K")
      (footprint "eagle-import:R0805")
      (libsource (lib "eagle-import") (part "R-EU_R0805"))
    )
    (comp (ref "R61")
      (value "1R")
      (footprint "eagle-import:R1206")
      (libsource (lib "eagle-import") (part "R-EU_R1206"))
    )
    (comp (ref "R62")
      (value "47K")
      (footprint "eagle-import:R0805")
      (libsource (lib "eagle-import") (part "R-EU_R0805"))
    )
    (comp (ref "R63")
      (value "8K2")
      (footprint "eagle-import:R0805")
      (libsource (lib "eagle-import") (part "R-EU_R0805"))
    )
    (comp (ref "R64")
      (value "39K 0.1%")
      (footprint "eagle-import:R0805")
      (libsource (lib "eagle-import") (part "R-EU_R0805"))
    )
    (comp (ref "R65")
      (value "47K")
      (footprint "eagle-import:R0805")
      (libsource (lib "eagle-import") (part "R-EU_R0805"))
    )
    (comp (ref "R66")
      (value "3K3")
      (footprint "eagle-import:R0805")
      (libsource (lib "eagle-import") (part "R-EU_R0805"))
    )
    (comp (ref "R67")
      (value "0R010 (low TCR)")
      (footprint "eagle-import:R_2512-4WIRE")
      (libsource (lib "eagle-import") (part "R-EU_4WIRE2512"))
    )
    (comp (ref "R68")
      (value "820R 0.1%")
      (footprint "eagle-import:R0805")
      (libsource (lib "eagle-import") (part "R-EU_R0805"))
    )
    (comp (ref "R115")
      (value "220R")
      (footprint "eagle-import:R0805")
      (libsource (lib "eagle-import") (part "R-EU_R0805"))
    )
    (comp (ref "R116")
      (value "470R")
      (footprint "eagle-import:R0805")
      (libsource (lib "eagle-import") (part "R-EU_R0805"))
    )
    (comp (ref "R118")
      (value "22K")
      (footprint "eagle-import:R0805")
      (libsource (lib "eagle-import") (part "R-EU_R0805"))
    )
    (comp (ref "ZD2")
      (value "MM3Z9V1T1G")
      (footprint "eagle-import:SOD323-R")
      (libsource (lib "eagle-import") (part "ZENER-DIODESOD323R"))
    )
    (comp (ref "C63")
      (value "330p")
      (footprint "eagle-import:C0805")
      (libsource (lib "eagle-import") (part "C-EUC0805"))
    )
    (comp (ref "C64")
      (value "4n7")
      (footprint "eagle-import:C0805")
      (libsource (lib "eagle-import") (part "C-EUC0805"))
    )
    (comp (ref "C65")
      (value "100n")
      (footprint "eagle-import:C0603")
      (libsource (lib "eagle-import") (part "C-EUC0603"))
    )
    (comp (ref "C66")
      (value "100n")
      (footprint "eagle-import:C0603")
      (libsource (lib "eagle-import") (part "C-EUC0603"))
    )
    (comp (ref "C67")
      (value "4u7")
      (footprint "eagle-import:C1206")
      (libsource (lib "eagle-import") (part "C-EUC1206"))
    )
    (comp (ref "C68")
      (value "100n")
      (footprint "eagle-import:C0603")
      (libsource (lib "eagle-import") (part "C-EUC0603"))
    )
    (comp (ref "C69")
      (value "4u7 tant.")
      (footprint "eagle-import:EC1206")
      (libsource (lib "eagle-import") (part "ECAP1206"))
    )
    (comp (ref "C70")
      (value "1u")
      (footprint "eagle-import:C0805")
      (libsource (lib "eagle-import") (part "C-EUC0805"))
    )
    (comp (ref "C71")
      (value "1u")
      (footprint "eagle-import:C0805")
      (libsource (lib "eagle-import") (part "C-EUC0805"))
    )
    (comp (ref "C72")
      (value "100n")
      (footprint "eagle-import:C0603")
      (libsource (lib "eagle-import") (part "C-EUC0603"))
    )
    (comp (ref "C73")
      (value "100n")
      (footprint "eagle-import:C0603")
      (libsource (lib "eagle-import") (part "C-EUC0603"))
    )
    (comp (ref "C74")
      (value "100n")
      (footprint "eagle-import:C0603")
      (libsource (lib "eagle-import") (part "C-EUC0603"))
    )
    (comp (ref "C75")
      (value "4n7")
      (footprint "eagle-import:C0805")
      (libsource (lib "eagle-import") (part "C-EUC0805"))
    )
    (comp (ref "C76")
      (value "4n7")
      (footprint "eagle-import:C0805")
      (libsource (lib "eagle-import") (part "C-EUC0805"))
    )
    (comp (ref "C77")
      (value "4n7")
      (footprint "eagle-import:C0805")
      (libsource (lib "eagle-import") (part "C-EUC0805"))
    )
    (comp (ref "C78")
      (value "4n7")
      (footprint "eagle-import:C0805")
      (libsource (lib "eagle-import") (part "C-EUC0805"))
    )
    (comp (ref "C79")
      (value "100n")
      (footprint "eagle-import:C0603")
      (libsource (lib "eagle-import") (part "C-EUC0603"))
    )
    (comp (ref "C80")
      (value "1u")
      (footprint "eagle-import:C0805")
      (libsource (lib "eagle-import") (part "C-EUC0805"))
    )
    (comp (ref "C81")
      (value "100n")
      (footprint "eagle-import:C0603")
      (libsource (lib "eagle-import") (part "C-EUC0603"))
    )
    (comp (ref "C82")
      (value "1u")
      (footprint "eagle-import:C0805")
      (libsource (lib "eagle-import") (part "C-EUC0805"))
    )
    (comp (ref "C83")
      (value "100n")
      (footprint "eagle-import:C0603")
      (libsource (lib "eagle-import") (part "C-EUC0603"))
    )
    (comp (ref "D15")
      (value "BAS316")
      (footprint "eagle-import:SOD323-R")
      (libsource (lib "eagle-import") (part "DIODESOD323R"))
    )
    (comp (ref "D16")
      (value "BAS316")
      (footprint "eagle-import:SOD323-R")
      (libsource (lib "eagle-import") (part "DIODESOD323R"))
    )
    (comp (ref "D17")
      (value "SKL14")
      (footprint "eagle-import:SOD123")
      (libsource (lib "eagle-import") (part "SCHOTTKYSOD123"))
    )
    (comp (ref "IC12")
      (value "74AUP1G74DC.125")
      (footprint "eagle-import:DCU8")
      (libsource (lib "eagle-import") (part "SN74LVC1G74DCTR-VSSOP"))
    )
    (comp (ref "IC13")
      (value "MCP23S17-E/SS")
      (footprint "eagle-import:SOP65P780X200-28N")
      (libsource (lib "eagle-import") (part "MCP23S17-E/SSSSOP"))
    )
    (comp (ref "IC14")
      (value "REF5025AIDR")
      (footprint "eagle-import:SOIC127P600X175-8N")
      (libsource (lib "eagle-import") (part "REF50XX"))
    )
    (comp (ref "IC15")
      (value "TC77-5.0MCTTR")
      (footprint "eagle-import:SOT23-5")
      (libsource (lib "eagle-import") (part "TC77"))
    )
    (comp (ref "IC16")
      (value "DAC8552IDGKR")
      (footprint "eagle-import:DGK8-M")
      (libsource (lib "eagle-import") (part "DAC8552_DGK_8M"))
    )
    (comp (ref "IC17")
      (value "SN74LVC1G3157DCKR")
      (footprint "eagle-import:SOT65P210X110-6N")
      (libsource (lib "eagle-import") (part "SN74LVC1G3157-DCK"))
    )
    (comp (ref "IC18")
      (value "ADS1120IPWR")
      (footprint "eagle-import:PW(R-PDSO-G16)")
      (libsource (lib "eagle-import") (part "ADS1120TSSOP-16"))
    )
    (comp (ref "I_SET")
      (value "JP2-NOCUT")
      (footprint "eagle-import:JP2-NOCUT")
      (libsource (lib "eagle-import") (part "JP2-NOCUT"))
    )
    (comp (ref "JP1")
      (value "JP2-NOCUT")
      (footprint "eagle-import:JP2-NOCUT")
      (libsource (lib "eagle-import") (part "JP2-NOCUT"))
    )
    (comp (ref "JP2")
      (value "JP2-CUT-0805")
      (footprint "eagle-import:R_0805")
      (libsource (lib "eagle-import") (part "JP2-CUT-0805"))
    )
    (comp (ref "LED1")
      (value "WP42WUM/EGW")
      (footprint "eagle-import:L-42WUM-1EGWT")
      (libsource (lib "eagle-import") (part "LED_L-42WUM/1EGWT"))
    )
    (comp (ref "LED2")
      (value "WP934MD/2LID")
      (footprint "eagle-import:WP934MD")
      (libsource (lib "eagle-import") (part "WP934MD/2LID"))
    )
    (comp (ref "OE")
      (value "JP2-NOCUT")
      (footprint "eagle-import:JP2-NOCUT")
      (libsource (lib "eagle-import") (part "JP2-NOCUT"))
    )
    (comp (ref "Q12")
      (value "BSS84P")
      (footprint "eagle-import:SOT95P237X112-3N")
      (fields (field (name "MPN") "IRLML2246TRPBF"))
      (libsource (lib "eagle-import") (part "IRLML2246TRPBF"))
    )
    (comp (ref "R69")
      (value "1K")
      (footprint "eagle-import:R0805")
      (libsource (lib "eagle-import") (part "R-EU_R0805"))
    )
    (comp (ref "R70")
      (value "4K7")
      (footprint "eagle-import:R0805")
      (libsource (lib "eagle-import") (part "R-EU_R0805"))
    )
    (comp (ref "R71")
      (value "10K")
      (footprint "eagle-import:R0805")
      (libsource (lib "eagle-import") (part "R-EU_R0805"))
    )
    (comp (ref "R72")
      (value "100K")
      (footprint "eagle-import:R0805")
      (libsource (lib "eagle-import") (part "R-EU_R0805"))
    )
    (comp (ref "R73")
      (value "270R")
      (footprint "eagle-import:R0805")
      (libsource (lib "eagle-import") (part "R-EU_R0805"))
    )
    (comp (ref "R74")
      (value "2K2")
      (footprint "eagle-import:R0805")
      (libsource (lib "eagle-import") (part "R-EU_R0805"))
    )
    (comp (ref "R75")
      (value "470R")
      (footprint "eagle-import:R0805")
      (libsource (lib "eagle-import") (part "R-EU_R0805"))
    )
    (comp (ref "R76")
      (value "470R")
      (footprint "eagle-import:R0805")
      (libsource (lib "eagle-import") (part "R-EU_R0805"))
    )
    (comp (ref "R77")
      (value "2K2")
      (footprint "eagle-import:R0805")
      (libsource (lib "eagle-import") (part "R-EU_R0805"))
    )
    (comp (ref "R78")
      (value "2K2")
      (footprint "eagle-import:R0805")
      (libsource (lib "eagle-import") (part "R-EU_R0805"))
    )
    (comp (ref "R79")
      (value "470R")
      (footprint "eagle-import:R0805")
      (libsource (lib "eagle-import") (part "R-EU_R0805"))
    )
    (comp (ref "R80")
      (value "2K2")
      (footprint "eagle-import:R0805")
      (libsource (lib "eagle-import") (part "R-EU_R0805"))
    )
    (comp (ref "R81")
      (value "2K2")
      (footprint "eagle-import:R0805")
      (libsource (lib "eagle-import") (part "R-EU_R0805"))
    )
    (comp (ref "R82")
      (value "10R")
      (footprint "eagle-import:R1206")
      (libsource (lib "eagle-import") (part "R-EU_R1206"))
    )
    (comp (ref "U_SET")
      (value "JP2-NOCUT")
      (footprint "eagle-import:JP2-NOCUT")
      (libsource (lib "eagle-import") (part "JP2-NOCUT"))
    )
    (comp (ref "X3")
      (value "691322110005")
      (footprint "eagle-import:MC1,5_5-G-3,5")
      (libsource (lib "eagle-import") (part "MC1,5/5-G-3,5"))
    )
    (comp (ref "ZD3")
      (value "SLVU2.8-TP")
      (footprint "eagle-import:SOT23")
      (libsource (lib "eagle-import") (part "SLVU2.8"))
    )
    (comp (ref "C1")
      (value "10n/200V")
      (footprint "eagle-import:C1206")
      (libsource (lib "eagle-import") (part "C-EUC1206"))
    )
    (comp (ref "C2")
      (value "HHXC630A330MHA0G")
      (footprint "eagle-import:CAPAE830X1050N")
      (libsource (lib "eagle-import") (part "ECAPSMD8.3MM/HA0"))
    )
    (comp (ref "C3")
      (value "10n/200V")
      (footprint "eagle-import:C1206")
      (libsource (lib "eagle-import") (part "C-EUC1206"))
    )
    (comp (ref "C4")
      (value "10n/200V")
      (footprint "eagle-import:C1206")
      (libsource (lib "eagle-import") (part "C-EUC1206"))
    )
    (comp (ref "C5")
      (value "4u7/100V")
      (footprint "eagle-import:C1210")
      (libsource (lib "eagle-import") (part "C-EUC1210"))
    )
    (comp (ref "C6")
      (value "4u7/100V")
      (footprint "eagle-import:C1210")
      (libsource (lib "eagle-import") (part "C-EUC1210"))
    )
    (comp (ref "C7")
      (value "1u/100V")
      (footprint "eagle-import:C1206")
      (libsource (lib "eagle-import") (part "C-EUC1206"))
    )
    (comp (ref "C8")
      (value "470n")
      (footprint "eagle-import:C0805")
      (libsource (lib "eagle-import") (part "C-EUC0805"))
    )
    (comp (ref "C9")
      (value "100n")
      (footprint "eagle-import:C0603")
      (libsource (lib "eagle-import") (part "C-EUC0603"))
    )
    (comp (ref "C10")
      (value "10u")
      (footprint "eagle-import:C1210")
      (libsource (lib "eagle-import") (part "C-EUC1210"))
    )
    (comp (ref "C11")
      (value "EEEFK1J101P")
      (footprint "eagle-import:CAPAE1030X1050N")
      (libsource (lib "eagle-import") (part "ECAP10X10"))
    )
    (comp (ref "C12")
      (value "470p")
      (footprint "eagle-import:C0805")
      (libsource (lib "eagle-import") (part "C-EUC0805"))
    )
    (comp (ref "C13")
      (value "EEEFK1H470P")
      (footprint "eagle-import:CAPAE830X1050N")
      (libsource (lib "eagle-import") (part "ECAPSMD8.3MM/HA0"))
    )
    (comp (ref "C14")
      (value "N.C.")
      (footprint "eagle-import:C0805")
      (libsource (lib "eagle-import") (part "C-EUC0805"))
    )
    (comp (ref "C15")
      (value "10u")
      (footprint "eagle-import:C1210")
      (libsource (lib "eagle-import") (part "C-EUC1210"))
    )
    (comp (ref "C16")
      (value "EEEFK1J101P")
      (footprint "eagle-import:CAPAE1030X1050N")
      (libsource (lib "eagle-import") (part "ECAP10X10"))
    )
    (comp (ref "C17")
      (value "33p")
      (footprint "eagle-import:C0805")
      (libsource (lib "eagle-import") (part "C-EUC0805"))
    )
    (comp (ref "C18")
      (value "6n8")
      (footprint "eagle-import:C0805")
      (libsource (lib "eagle-import") (part "C-EUC0805"))
    )
    (comp (ref "C19")
      (value "470p")
      (footprint "eagle-import:C0805")
      (libsource (lib "eagle-import") (part "C-EUC0805"))
    )
    (comp (ref "D1")
      (value "BAS316")
      (footprint "eagle-import:SOD323-R")
      (libsource (lib "eagle-import") (part "DIODESOD323R"))
    )
    (comp (ref "D2")
      (value "STPS15H100")
      (footprint "eagle-import:TO252-L")
      (libsource (lib "eagle-import") (part "SCHOTTKY-DUAL_A_L"))
    )
    (comp (ref "D3")
      (value "BAS316")
      (footprint "eagle-import:SOD323-R")
      (libsource (lib "eagle-import") (part "DIODESOD323R"))
    )
    (comp (ref "FM1")
      (value "FIDUCIAL_2")
      (footprint "eagle-import:FIDUCIAL_DUAL")
      (libsource (lib "eagle-import") (part "FIDUCIAL_2"))
    )
    (comp (ref "FM2")
      (value "FIDUCIAL_2")
      (footprint "eagle-import:FIDUCIAL_DUAL")
      (libsource (lib "eagle-import") (part "FIDUCIAL_2"))
    )
    (comp (ref "FM3")
      (value "FIDUCIAL_2")
      (footprint "eagle-import:FIDUCIAL_DUAL")
      (libsource (lib "eagle-import") (part "FIDUCIAL_2"))
    )
    (comp (ref "GND")
      (value "PCB_TEST_TABSHIELD")
      (footprint "eagle-import:PCB_SHIELD_TAB")
      (libsource (lib "eagle-import") (part "PCB_TEST_TABSHIELD"))
    )
    (comp (ref "IC1")
      (value "LTC3864EMSE#PBF")
      (footprint "eagle-import:LTC_05-08-1666")
      (libsource (lib "eagle-import") (part "LTC3864"))
    )
    (comp (ref "J1")
      (value "4907")
      (footprint "eagle-import:PCB_TAB-4907")
      (libsource (lib "eagle-import") (part "PCB_TAB-4907"))
    )
    (comp (ref "L1")
      (value "RN112-4-02-0M7")
      (footprint "eagle-import:RN112")
      (libsource (lib "eagle-import") (part "RN112"))
    )
    (comp (ref "L2")
      (value "125CDMCCDS-330MC")
      (footprint "eagle-import:125CDMCC_DS")
      (libsource (lib "eagle-import") (part "125CDMCC/DS"))
    )
    (comp (ref "L3")
      (value "VLS6045AF-3R3N")
      (footprint "eagle-import:COILCRAFT_HPI0630")
      (libsource (lib "eagle-import") (part "COILCRAFT_HPI0630"))
    )
    (comp (ref "OSHWA")
      (value "HR000002")
      (footprint "eagle-import:CERT-SMALL-SILK")
      (libsource (lib "eagle-import") (part "OSHWA-CERT-SMALL"))
    )
    (comp (ref "Q1")
      (value "SUD19P06-60")
      (footprint "eagle-import:TO229P990X239-3N")
      (libsource (lib "eagle-import") (part "P-MOSFETDPAK"))
    )
    (comp (ref "Q2")
      (value "MMBT5401")
      (footprint "eagle-import:SOT23-BEC")
      (libsource (lib "eagle-import") (part "-PNP-SOT23-BECBC857B"))
    )
    (comp (ref "R1")
      (value "N.C.")
      (footprint "eagle-import:R2512")
      (libsource (lib "eagle-import") (part "R-EU_R2512"))
    )
    (comp (ref "R2")
      (value "10K")
      (footprint "eagle-import:R0805")
      (libsource (lib "eagle-import") (part "R-EU_R0805"))
    )
    (comp (ref "R3")
      (value "R008/2-3W")
      (footprint "eagle-import:R2512")
      (libsource (lib "eagle-import") (part "R-EU_R2512"))
    )
    (comp (ref "R4")
      (value "15R")
      (footprint "eagle-import:R2010")
      (libsource (lib "eagle-import") (part "R-EU_R2010"))
    )
    (comp (ref "R5")
      (value "10R")
      (footprint "eagle-import:R1206")
      (libsource (lib "eagle-import") (part "R-EU_R1206"))
    )
    (comp (ref "R6")
      (value "10K")
      (footprint "eagle-import:R0805")
      (libsource (lib "eagle-import") (part "R-EU_R0805"))
    )
    (comp (ref "R7")
      (value "100K")
      (footprint "eagle-import:R0805")
      (libsource (lib "eagle-import") (part "R-EU_R0805"))
    )
    (comp (ref "R8")
      (value "1K")
      (footprint "eagle-import:R0805")
      (libsource (lib "eagle-import") (part "R-EU_R0805"))
    )
    (comp (ref "R9")
      (value "330K")
      (footprint "eagle-import:R0805")
      (libsource (lib "eagle-import") (part "R-EU_R0805"))
    )
    (comp (ref "R10")
      (value "100K")
      (footprint "eagle-import:R0805")
      (libsource (lib "eagle-import") (part "R-EU_R0805"))
    )
    (comp (ref "R11")
      (value "4K7")
      (footprint "eagle-import:R0805")
      (libsource (lib "eagle-import") (part "R-EU_R0805"))
    )
    (comp (ref "SH1")
      (value "SHORTNOHOLE")
      (footprint "eagle-import:SHORT_NOHOLE")
      (libsource (lib "eagle-import") (part "SHORTNOHOLE"))
    )
    (comp (ref "SH2")
      (value "Pgnd to Pout- short")
      (footprint "eagle-import:SHORT_NOHOLE")
      (libsource (lib "eagle-import") (part "SHORTNOHOLE"))
    )
    (comp (ref "SH3")
      (value "Sgnd to Pgnd short")
      (footprint "eagle-import:SHORT_NOHOLE")
      (libsource (lib "eagle-import") (part "SHORTNOHOLE"))
    )
    (comp (ref "X1")
      (value "39-30-1020")
      (footprint "eagle-import:MINIFIT_39301020")
      (libsource (lib "eagle-import") (part "MINIFIT_39301020"))
    )
    (comp (ref "ZD1")
      (value "SMAJ51A")
      (footprint "eagle-import:DO214AA")
      (libsource (lib "eagle-import") (part "P6SMB68A"))
    )
    (comp (ref "C90")
      (value "10n")
      (footprint "eagle-import:C0805")
      (libsource (lib "eagle-import") (part "C-EUC0805"))
    )
    (comp (ref "C91")
      (value "470n")
      (footprint "eagle-import:C0805")
      (libsource (lib "eagle-import") (part "C-EUC0805"))
    )
    (comp (ref "C92")
      (value "HHXC630A330MHA0G")
      (footprint "eagle-import:CAPAE830X1050N")
      (libsource (lib "eagle-import") (part "ECAPSMD8.3MM/HA0"))
    )
    (comp (ref "C93")
      (value "10n/200V")
      (footprint "eagle-import:C1206")
      (libsource (lib "eagle-import") (part "C-EUC1206"))
    )
    (comp (ref "C94")
      (value "N.C.")
      (footprint "eagle-import:ECAP2_5")
      (libsource (lib "eagle-import") (part "ECAP2G/5"))
    )
    (comp (ref "C95")
      (value "N.C.")
      (footprint "eagle-import:C0805")
      (libsource (lib "eagle-import") (part "C-EUC0805"))
    )
    (comp (ref "C96")
      (value "N.C.")
      (footprint "eagle-import:C0805")
      (libsource (lib "eagle-import") (part "C-EUC0805"))
    )
    (comp (ref "C97")
      (value "10n/200V")
      (footprint "eagle-import:C1206")
      (libsource (lib "eagle-import") (part "C-EUC1206"))
    )
    (comp (ref "C98")
      (value "10n")
      (footprint "eagle-import:C0805")
      (libsource (lib "eagle-import") (part "C-EUC0805"))
    )
    (comp (ref "D20")
      (value "BAS316")
      (footprint "eagle-import:SOD323-R")
      (libsource (lib "eagle-import") (part "DIODESOD323R"))
    )
    (comp (ref "F1")
      (value "ZH32")
      (footprint "eagle-import:ZH32")
      (libsource (lib "eagle-import") (part "ZH32"))
    )
    (comp (ref "F2")
      (value "ZH32")
      (footprint "eagle-import:ZH32")
      (libsource (lib "eagle-import") (part "ZH32"))
    )
    (comp (ref "J2")
      (value "FCR7350R")
      (footprint "eagle-import:S16N-PC")
      (libsource (lib "eagle-import") (part "BINDING_POSTCLIFF"))
    )
    (comp (ref "J3")
      (value "FCR7350B")
      (footprint "eagle-import:S16N-PC")
      (libsource (lib "eagle-import") (part "BINDING_POSTCLIFF"))
    )
    (comp (ref "JP3")
      (value "JP2-CUT-0805")
      (footprint "eagle-import:R_0805")
      (libsource (lib "eagle-import") (part "JP2-CUT-0805"))
    )
    (comp (ref "JP4")
      (value "JP2-CUT-0805")
      (footprint "eagle-import:R_0805")
      (libsource (lib "eagle-import") (part "JP2-CUT-0805"))
    )
    (comp (ref "K1")
      (value "G6K-2F-5DC")
      (footprint "eagle-import:G6K-2F")
      (fields
        (field (name "MF") "OMRON COMPONENTS USA")
        (field (name "MPN") "G6K-2F DC24")
        (field (name "MF_1") "OMRON COMPONENTS USA")
        (field (name "MPN_1") "G6K-2F DC24")
        (field (name "OC_FARNELL") "1690427")
        (field (name "OC_NEWARK") "36K7467")
      )
      (libsource (lib "eagle-import") (part "G6K-2F"))
    )
    (comp (ref "Q20")
      (value "MMBT5401")
      (footprint "eagle-import:SOT23-BEC")
      (libsource (lib "eagle-import") (part "-PNP-SOT23-BECBC857B"))
    )
    (comp (ref "Q21")
      (value "MMBT5551")
      (footprint "eagle-import:SOT23-BEC")
      (libsource (lib "eagle-import") (part "-NPN-SOT23-BECMMBT5551LT1"))
    )
    (comp (ref "Q22")
      (value "MMBT5551")
      (footprint "eagle-import:SOT23-BEC")
      (libsource (lib "eagle-import") (part "-NPN-SOT23-BECMMBT5551LT1"))
    )
    (comp (ref "Q23")
      (value "2N7002")
      (footprint "eagle-import:SOT103P240X110-3N")
      (fields
        (field (name "MPN") "2N7002-7-F")
        (field (name "MPN_1") "2N7002-7-F")
        (field (name "OC_FARNELL") "1713823")
        (field (name "OC_NEWARK") "25R5679")
        (field (name "PACKAGE") "SOT-23-3")
        (field (name "SUPPLIER") "DIODES INC.")
      )
      (libsource (lib "eagle-import") (part "2N7002"))
    )
    (comp (ref "R104")
      (value "330R")
      (footprint "eagle-import:R0805")
      (libsource (lib "eagle-import") (part "R-EU_R0805"))
    )
    (comp (ref "R105")
      (value "750R")
      (footprint "eagle-import:R0805")
      (libsource (lib "eagle-import") (part "R-EU_R0805"))
    )
    (comp (ref "R106")
      (value "3K3")
      (footprint "eagle-import:R0805")
      (libsource (lib "eagle-import") (part "R-EU_R0805"))
    )
    (comp (ref "R107")
      (value "10K")
      (footprint "eagle-import:R0805")
      (libsource (lib "eagle-import") (part "R-EU_R0805"))
    )
    (comp (ref "R108")
      (value "10K")
      (footprint "eagle-import:R0805")
      (libsource (lib "eagle-import") (part "R-EU_R0805"))
    )
    (comp (ref "R109")
      (value "1R")
      (footprint "eagle-import:R1206")
      (libsource (lib "eagle-import") (part "R-EU_R1206"))
    )
    (comp (ref "R110")
      (value "750R")
      (footprint "eagle-import:R0805")
      (libsource (lib "eagle-import") (part "R-EU_R0805"))
    )
    (comp (ref "R111")
      (value "47K")
      (footprint "eagle-import:R0805")
      (libsource (lib "eagle-import") (part "R-EU_R0805"))
    )
    (comp (ref "R112")
      (value "330R")
      (footprint "eagle-import:R0805")
      (libsource (lib "eagle-import") (part "R-EU_R0805"))
    )
    (comp (ref "R113")
      (value "470R")
      (footprint "eagle-import:R0805")
      (libsource (lib "eagle-import") (part "R-EU_R0805"))
    )
    (comp (ref "R114")
      (value "100K")
      (footprint "eagle-import:R0805")
      (libsource (lib "eagle-import") (part "R-EU_R0805"))
    )
    (comp (ref "X4")
      (value "DS1024-2*10R0")
      (footprint "eagle-import:SSW-110-02-T-D-RA")
      (libsource (lib "eagle-import") (part "SSW-110-02-T-D-RA"))
    )
    (comp (ref "ZD5")
      (value "SMAJ51A")
      (footprint "eagle-import:DO214AA")
      (libsource (lib "eagle-import") (part "P6SMB68A"))
    )
  )
  (nets
    (net (code "1") (name "+3V3") (class "Default")
      (node (ref "C30") (pin "1") (pinfunction "1_1") (pintype "passive"))
      (node (ref "C35") (pin "1") (pinfunction "1_1") (pintype "passive"))
      (node (ref "C38") (pin "2") (pinfunction "2_2") (pintype "passive"))
      (node (ref "IC3") (pin "1") (pinfunction "VDD1_1") (pintype "passive"))
      (node (ref "IC3") (pin "7") (pinfunction "EN1_7") (pintype "input"))
      (node (ref "IC7") (pin "1") (pinfunction "VDD1_1") (pintype "passive"))
      (node (ref "IC7") (pin "7") (pinfunction "EN1_7") (pintype "input"))
      (node (ref "IC8") (pin "8") (pinfunction "VCC_8") (pintype "power_in"))
      (node (ref "R22") (pin "1") (pinfunction "1_1") (pintype "passive"))
      (node (ref "R23") (pin "1") (pinfunction "1_1") (pintype "passive"))
      (node (ref "R24") (pin "1") (pinfunction "1_1") (pintype "passive"))
      (node (ref "X2") (pin "1") (pinfunction "1_1") (pintype "passive"))
    )
    (net (code "2") (name "+5V") (class "Default")
      (node (ref "C31") (pin "2") (pinfunction "2_2") (pintype "passive"))
      (node (ref "C32") (pin "1") (pinfunction "1_1") (pintype "passive"))
      (node (ref "C36") (pin "2") (pinfunction "2_2") (pintype "passive"))
      (node (ref "C63") (pin "2") (pinfunction "2_2") (pintype "passive"))
      (node (ref "C64") (pin "2") (pinfunction "2_2") (pintype "passive"))
      (node (ref "C65") (pin "2") (pinfunction "2_2") (pintype "passive"))
      (node (ref "C66") (pin "1") (pinfunction "1_1") (pintype "passive"))
      (node (ref "C68") (pin "1") (pinfunction "1_1") (pintype "passive"))
      (node (ref "C79") (pin "2") (pinfunction "2_2") (pintype "passive"))
      (node (ref "C80") (pin "2") (pinfunction "2_2") (pintype "passive"))
      (node (ref "D20") (pin "C") (pinfunction "C_C") (pintype "passive"))
      (node (ref "FB2") (pin "P$2") (pinfunction "2_P$2") (pintype "passive"))
      (node (ref "IC12") (pin "7") (pinfunction "~{PRE}_7") (pintype "input"))
      (node (ref "IC12") (pin "8") (pinfunction "VDD_8") (pintype "power_in"))
      (node (ref "IC13") (pin "9") (pinfunction "VDD_9") (pintype "power_in"))
      (node (ref "IC15") (pin "5") (pinfunction "VDD_5") (pintype "passive"))
      (node (ref "IC18") (pin "13") (pinfunction "DVDD_13") (pintype "power_in"))
      (node (ref "IC3") (pin "10") (pinfunction "EN2_10") (pintype "input"))
      (node (ref "IC3") (pin "16") (pinfunction "VDD2_16") (pintype "passive"))
      (node (ref "IC4") (pin "8") (pinfunction "VCC_8") (pintype "passive"))
      (node (ref "IC7") (pin "10") (pinfunction "EN2_10") (pintype "input"))
      (node (ref "IC7") (pin "16") (pinfunction "VDD2_16") (pintype "passive"))
      (node (ref "K1") (pin "1") (pinfunction "+_1") (pintype "passive"))
      (node (ref "LED2") (pin "TA") (pinfunction "A_TA") (pintype "passive"))
      (node (ref "LED3") (pin "BA") (pinfunction "A_BA") (pintype "passive"))
      (node (ref "LED3") (pin "TA") (pinfunction "A_TA") (pintype "passive"))
      (node (ref "Q12") (pin "2") (pinfunction "S_2") (pintype "passive"))
      (node (ref "R107") (pin "2") (pinfunction "2_2") (pintype "passive"))
      (node (ref "R17") (pin "1") (pinfunction "1_1") (pintype "passive"))
      (node (ref "R69") (pin "1") (pinfunction "1_1") (pintype "passive"))
      (node (ref "R70") (pin "1") (pinfunction "1_1") (pintype "passive"))
      (node (ref "R71") (pin "1") (pinfunction "1_1") (pintype "passive"))
      (node (ref "R72") (pin "1") (pinfunction "1_1") (pintype "passive"))
      (node (ref "R84") (pin "2") (pinfunction "2_2") (pintype "passive"))
      (node (ref "R98") (pin "2") (pinfunction "2_2") (pintype "passive"))
    )
    (net (code "3") (name "+VNR") (class "Default")
      (node (ref "C27") (pin "1") (pinfunction "1_1") (pintype "passive"))
      (node (ref "IC5") (pin "8") (pinfunction "VI_8") (pintype "input"))
      (node (ref "R14") (pin "1") (pinfunction "1_1") (pintype "passive"))
    )
    (net (code "4") (name "+VREF") (class "Default")
      (node (ref "C69") (pin "+") (pinfunction "+_+") (pintype "passive"))
      (node (ref "C73") (pin "2") (pinfunction "2_2") (pintype "passive"))
      (node (ref "C83") (pin "2") (pinfunction "2_2") (pintype "passive"))
      (node (ref "IC14") (pin "6") (pinfunction "VOUT_6") (pintype "output"))
      (node (ref "IC16") (pin "2") (pinfunction "VREF_2") (pintype "input"))
      (node (ref "IC18") (pin "9") (pinfunction "REFP0_9") (pintype "input"))
      (node (ref "R31") (pin "1") (pinfunction "1_1") (pintype "passive"))
    )
    (net (code "5") (name "-9V") (class "Default")
      (node (ref "C21") (pin "1") (pinfunction "1_1") (pintype "passive"))
      (node (ref "IC6") (pin "2") (pinfunction "IN_2") (pintype "input"))
      (node (ref "IC6") (pin "3") (pinfunction "IN_3") (pintype "input"))
      (node (ref "IC6") (pin "6") (pinfunction "IN_6") (pintype "input"))
      (node (ref "IC6") (pin "7") (pinfunction "IN_7") (pintype "input"))
      (node (ref "R12") (pin "1") (pinfunction "1_1") (pintype "passive"))
      (node (ref "R28") (pin "1") (pinfunction "1_1") (pintype "passive"))
      (node (ref "R38") (pin "2") (pinfunction "2_2") (pintype "passive"))
      (node (ref "R39") (pin "2") (pinfunction "2_2") (pintype "passive"))
    )
    (net (code "6") (name "AUX_USET_SW") (class "Default")
      (node (ref "IC13") (pin "4") (pinfunction "GPB3_4") (pintype "bidirectional"))
      (node (ref "IC17") (pin "6") (pinfunction "CTRL_6") (pintype "input"))
      (node (ref "LED2") (pin "BA") (pinfunction "A_BA") (pintype "passive"))
    )
    (net (code "7") (name "CC_ACTIVE") (class "Default")
      (node (ref "IC13") (pin "22") (pinfunction "GPA1_22") (pintype "bidirectional"))
      (node (ref "Q16") (pin "1") (pinfunction "G_1") (pintype "passive"))
      (node (ref "Q27") (pin "1") (pinfunction "G_1") (pintype "passive"))
      (node (ref "R100") (pin "2") (pinfunction "2_2") (pintype "passive"))
      (node (ref "R98") (pin "1") (pinfunction "1_1") (pintype "passive"))
    )
    (net (code "8") (name "CSA") (class "Default")
      (node (ref "IC3") (pin "13") (pinfunction "B2_13") (pintype "output"))
      (node (ref "IC4") (pin "1") (pinfunction "A_1") (pintype "input"))
    )
    (net (code "9") (name "CSB") (class "Default")
      (node (ref "IC3") (pin "12") (pinfunction "B3_12") (pintype "output"))
      (node (ref "IC4") (pin "2") (pinfunction "B_2") (pintype "input"))
    )
    (net (code "10") (name "CS_ADC") (class "Default")
      (node (ref "IC18") (pin "2") (pinfunction "~{CS}_2") (pintype "input"))
      (node (ref "RN1") (pin "7") (pinfunction "2_7") (pintype "passive"))
    )
    (net (code "11") (name "CS_DAC") (class "Default")
      (node (ref "IC16") (pin "5") (pinfunction "~{SYNC}_5") (pintype "input"))
      (node (ref "RN1") (pin "8") (pinfunction "2_8") (pintype "passive"))
    )
    (net (code "12") (name "CS_IOEXP") (class "Default")
      (node (ref "IC13") (pin "11") (pinfunction "~{CS}_11") (pintype "input"))
      (node (ref "RN1") (pin "6") (pinfunction "2_6") (pintype "passive"))
    )
    (net (code "13") (name "CURR_5A") (class "Default")
      (node (ref "IC13") (pin "28") (pinfunction "GPA7_28") (pintype "bidirectional"))
      (node (ref "IC21") (pin "6") (pinfunction "CTRL_6") (pintype "input"))
      (node (ref "Q11") (pin "4") (pinfunction "G_4") (pintype "passive"))
      (node (ref "R65") (pin "2") (pinfunction "2_2") (pintype "passive"))
    )
    (net (code "14") (name "CURR_50MA") (class "Default")
      (node (ref "IC13") (pin "27") (pinfunction "GPA6_27") (pintype "bidirectional"))
      (node (ref "Q10") (pin "4") (pinfunction "G_4") (pintype "passive"))
      (node (ref "R60") (pin "2") (pinfunction "2_2") (pintype "passive"))
    )
    (net (code "15") (name "CV_ACTIVE") (class "Default")
      (node (ref "IC13") (pin "23") (pinfunction "GPA2_23") (pintype "bidirectional"))
      (node (ref "Q15") (pin "1") (pinfunction "G_1") (pintype "passive"))
      (node (ref "R84") (pin "1") (pinfunction "1_1") (pintype "passive"))
      (node (ref "R88") (pin "2") (pinfunction "2_2") (pintype "passive"))
    )
    (net (code "16") (name "DC+") (class "Default")
      (node (ref "C1") (pin "2") (pinfunction "2_2") (pintype "passive"))
      (node (ref "L1") (pin "1") (pinfunction "1_1") (pintype "passive"))
      (node (ref "R1") (pin "2") (pinfunction "2_2") (pintype "passive"))
      (node (ref "X1") (pin "1") (pinfunction "1_1") (pintype "passive"))
    )
    (net (code "17") (name "DC-") (class "Default")
      (node (ref "C1") (pin "1") (pinfunction "1_1") (pintype "passive"))
      (node (ref "L1") (pin "3") (pinfunction "1_3") (pintype "passive"))
      (node (ref "R1") (pin "1") (pinfunction "1_1") (pintype "passive"))
      (node (ref "X1") (pin "2") (pinfunction "1_2") (pintype "passive"))
    )
    (net (code "18") (name "DC_OUT") (class "Default")
      (node (ref "C2") (pin "+") (pinfunction "+_+") (pintype "passive"))
      (node (ref "C22") (pin "1") (pinfunction "1_1") (pintype "passive"))
      (node (ref "C23") (pin "1") (pinfunction "1_1") (pintype "passive"))
      (node (ref "C4") (pin "2") (pinfunction "2_2") (pintype "passive"))
      (node (ref "C5") (pin "1") (pinfunction "1_1") (pintype "passive"))
      (node (ref "C6") (pin "1") (pinfunction "1_1") (pintype "passive"))
      (node (ref "C7") (pin "1") (pinfunction "1_1") (pintype "passive"))
      (node (ref "C8") (pin "2") (pinfunction "2_2") (pintype "passive"))
      (node (ref "IC1") (pin "11") (pinfunction "VIN_11") (pintype "passive"))
      (node (ref "IC2") (pin "2") (pinfunction "VIN_2") (pintype "power_in"))
      (node (ref "L1") (pin "2") (pinfunction "2_2") (pintype "passive"))
      (node (ref "R13") (pin "2") (pinfunction "2_2") (pintype "passive"))
      (node (ref "R3") (pin "1") (pinfunction "1_1") (pintype "passive"))
      (node (ref "ZD1") (pin "C") (pinfunction "C_C") (pintype "passive"))
    )
    (net (code "19") (name "DIB_A0") (class "Default")
      (node (ref "IC8") (pin "1") (pinfunction "A0_1") (pintype "input"))
      (node (ref "R24") (pin "2") (pinfunction "2_2") (pintype "passive"))
      (node (ref "X2") (pin "17") (pinfunction "1_17") (pintype "passive"))
    )
    (net (code "20") (name "DIB_A1") (class "Default")
      (node (ref "IC8") (pin "2") (pinfunction "A1_2") (pintype "input"))
      (node (ref "R23") (pin "2") (pinfunction "2_2") (pintype "passive"))
      (node (ref "X2") (pin "19") (pinfunction "1_19") (pintype "passive"))
    )
    (net (code "21") (name "DIB_A2") (class "Default")
      (node (ref "IC8") (pin "3") (pinfunction "A2_3") (pintype "input"))
      (node (ref "R22") (pin "2") (pinfunction "2_2") (pintype "passive"))
      (node (ref "X2") (pin "18") (pinfunction "1_18") (pintype "passive"))
    )
    (net (code "22") (name "DIB_CSA") (class "Default")
      (node (ref "IC3") (pin "4") (pinfunction "A2_4") (pintype "input"))
      (node (ref "X2") (pin "9") (pinfunction "1_9") (pintype "passive"))
    )
    (net (code "23") (name "DIB_CSB") (class "Default")
      (node (ref "IC3") (pin "5") (pinfunction "A3_5") (pintype "input"))
      (node (ref "X2") (pin "12") (pinfunction "1_12") (pintype "passive"))
    )
    (net (code "24") (name "DIB_IRQ") (class "Default")
      (node (ref "IC7") (pin "6") (pinfunction "A4_6") (pintype "output"))
      (node (ref "X2") (pin "10") (pinfunction "1_10") (pintype "passive"))
    )
    (net (code "25") (name "DIB_MISO") (class "Default")
      (node (ref "IC3") (pin "6") (pinfunction "A4_6") (pintype "output"))
      (node (ref "X2") (pin "14") (pinfunction "1_14") (pintype "passive"))
    )
    (net (code "26") (name "DIB_MOSI") (class "Default")
      (node (ref "IC7") (pin "3") (pinfunction "A1_3") (pintype "input"))
      (node (ref "X2") (pin "15") (pinfunction "1_15") (pintype "passive"))
    )
    (net (code "27") (name "DIB_NRESET") (class "Default")
      (node (ref "IC7") (pin "5") (pinfunction "A3_5") (pintype "input"))
      (node (ref "X2") (pin "4") (pinfunction "1_4") (pintype "passive"))
    )
    (net (code "28") (name "DIB_SCL") (class "Default")
      (node (ref "IC8") (pin "6") (pinfunction "SCL_6") (pintype "bidirectional"))
      (node (ref "X2") (pin "5") (pinfunction "1_5") (pintype "passive"))
    )
    (net (code "29") (name "DIB_SCLK") (class "Default")
      (node (ref "IC3") (pin "3") (pinfunction "A1_3") (pintype "input"))
      (node (ref "X2") (pin "13") (pinfunction "1_13") (pintype "passive"))
    )
    (net (code "30") (name "DIB_SDA") (class "Default")
      (node (ref "IC8") (pin "5") (pinfunction "SDA_5") (pintype "bidirectional"))
      (node (ref "X2") (pin "8") (pinfunction "1_8") (pintype "passive"))
    )
    (net (code "31") (name "FB") (class "Default")
      (node (ref "C19") (pin "1") (pinfunction "1_1") (pintype "passive"))
      (node (ref "IC1") (pin "5") (pinfunction "VFB_5") (pintype "input"))
      (node (ref "Q2") (pin "C") (pinfunction "C_C") (pintype "passive"))
      (node (ref "R11") (pin "1") (pinfunction "1_1") (pintype "passive"))
      (node (ref "R9") (pin "2") (pinfunction "2_2") (pintype "passive"))
    )
    (net (code "32") (name "GCOM") (class "Default")
      (node (ref "IC10") (pin "6") (pinfunction "-IN_6") (pintype "input"))
      (node (ref "IC10") (pin "7") (pinfunction "OUT_7") (pintype "output"))
      (node (ref "R41") (pin "1") (pinfunction "1_1") (pintype "passive"))
      (node (ref "R58") (pin "1") (pinfunction "1_1") (pintype "passive"))
    )
    (net (code "33") (name "GND") (class "Default")
      (node (ref "C20") (pin "2") (pinfunction "2_2") (pintype "passive"))
      (node (ref "C21") (pin "2") (pinfunction "2_2") (pintype "passive"))
      (node (ref "C22") (pin "2") (pinfunction "2_2") (pintype "passive"))
      (node (ref "C23") (pin "2") (pinfunction "2_2") (pintype "passive"))
      (node (ref "C26") (pin "2") (pinfunction "2_2") (pintype "passive"))
      (node (ref "C27") (pin "2") (pinfunction "2_2") (pintype "passive"))
      (node (ref "C28") (pin "2") (pinfunction "2_2") (pintype "passive"))
      (node (ref "C29") (pin "1") (pinfunction "1_1") (pintype "passive"))
      (node (ref "C31") (pin "1") (pinfunction "1_1") (pintype "passive"))
      (node (ref "C32") (pin "2") (pinfunction "2_2") (pintype "passive"))
      (node (ref "C33") (pin "1") (pinfunction "1_1") (pintype "passive"))
      (node (ref "C34") (pin "2") (pinfunction "2_2") (pintype "passive"))
      (node (ref "C36") (pin "1") (pinfunction "1_1") (pintype "passive"))
      (node (ref "C37") (pin "1") (pinfunction "1_1") (pintype "passive"))
      (node (ref "C39") (pin "2") (pinfunction "2_2") (pintype "passive"))
      (node (ref "C42") (pin "2") (pinfunction "2_2") (pintype "passive"))
      (node (ref "C48") (pin "2") (pinfunction "2_2") (pintype "passive"))
      (node (ref "C49") (pin "1") (pinfunction "1_1") (pintype "passive"))
      (node (ref "C50") (pin "2") (pinfunction "2_2") (pintype "passive"))
      (node (ref "C51") (pin "1") (pinfunction "1_1") (pintype "passive"))
      (node (ref "C52") (pin "1") (pinfunction "1_1") (pintype "passive"))
      (node (ref "C53") (pin "1") (pinfunction "1_1") (pintype "passive"))
      (node (ref "C54") (pin "1") (pinfunction "1_1") (pintype "passive"))
      (node (ref "C56") (pin "1") (pinfunction "1_1") (pintype "passive"))
      (node (ref "C57") (pin "2") (pinfunction "2_2") (pintype "passive"))
      (node (ref "C58") (pin "1") (pinfunction "1_1") (pintype "passive"))
      (node (ref "C59") (pin "1") (pinfunction "1_1") (pintype "passive"))
      (node (ref "C62") (pin "2") (pinfunction "2_2") (pintype "passive"))
      (node (ref "C65") (pin "1") (pinfunction "1_1") (pintype "passive"))
      (node (ref "C66") (pin "2") (pinfunction "2_2") (pintype "passive"))
      (node (ref "C67") (pin "2") (pinfunction "2_2") (pintype "passive"))
      (node (ref "C68") (pin "2") (pinfunction "2_2") (pintype "passive"))
      (node (ref "C69") (pin "-") (pinfunction "-_-") (pintype "passive"))
      (node (ref "C70") (pin "2") (pinfunction "2_2") (pintype "passive"))
      (node (ref "C71") (pin "2") (pinfunction "2_2") (pintype "passive"))
      (node (ref "C72") (pin "1") (pinfunction "1_1") (pintype "passive"))
      (node (ref "C73") (pin "1") (pinfunction "1_1") (pintype "passive"))
      (node (ref "C74") (pin "2") (pinfunction "2_2") (pintype "passive"))
      (node (ref "C75") (pin "1") (pinfunction "1_1") (pintype "passive"))
      (node (ref "C76") (pin "1") (pinfunction "1_1") (pintype "passive"))
      (node (ref "C77") (pin "2") (pinfunction "2_2") (pintype "passive"))
      (node (ref "C78") (pin "1") (pinfunction "1_1") (pintype "passive"))
      (node (ref "C79") (pin "1") (pinfunction "1_1") (pintype "passive"))
      (node (ref "C80") (pin "1") (pinfunction "1_1") (pintype "passive"))
      (node (ref "C81") (pin "1") (pinfunction "1_1") (pintype "passive"))
      (node (ref "C82") (pin "1") (pinfunction "1_1") (pintype "passive"))
      (node (ref "C83") (pin "1") (pinfunction "1_1") (pintype "passive"))
      (node (ref "C84") (pin "2") (pinfunction "2_2") (pintype "passive"))
      (node (ref "C85") (pin "1") (pinfunction "1_1") (pintype "passive"))
      (node (ref "C86") (pin "1") (pinfunction "1_1") (pintype "passive"))
      (node (ref "C88") (pin "1") (pinfunction "1_1") (pintype "passive"))
      (node (ref "C89") (pin "1") (pinfunction "1_1") (pintype "passive"))
      (node (ref "D10") (pin "C") (pinfunction "C_C") (pintype "passive"))
      (node (ref "D17") (pin "A") (pinfunction "A_A") (pintype "passive"))
      (node (ref "D19") (pin "C") (pinfunction "C_C") (pintype "passive"))
      (node (ref "D5") (pin "A") (pinfunction "A_A") (pintype "passive"))
      (node (ref "D6") (pin "A") (pinfunction "A_A") (pintype "passive"))
      (node (ref "D7") (pin "C") (pinfunction "C_C") (pintype "passive"))
      (node (ref "D9") (pin "C") (pinfunction "C_C") (pintype "passive"))
      (node (ref "GND") (pin "1") (pinfunction "P$1_1") (pintype "bidirectional"))
      (node (ref "IC12") (pin "4") (pinfunction "VSS_4") (pintype "power_in"))
      (node (ref "IC13") (pin "10") (pinfunction "VSS_10") (pintype "power_in"))
      (node (ref "IC13") (pin "15") (pinfunction "A0_15") (pintype "input"))
      (node (ref "IC13") (pin "16") (pinfunction "A1_16") (pintype "input"))
      (node (ref "IC13") (pin "17") (pinfunction "A2_17") (pintype "input"))
      (node (ref "IC14") (pin "4") (pinfunction "GND_4") (pintype "passive"))
      (node (ref "IC15") (pin "2") (pinfunction "GND_2") (pintype "passive"))
      (node (ref "IC16") (pin "8") (pinfunction "GND_8") (pintype "power_in"))
      (node (ref "IC17") (pin "2") (pinfunction "GND_2") (pintype "passive"))
      (node (ref "IC18") (pin "3") (pinfunction "CLK_3") (pintype "bidirectional"))
      (node (ref "IC18") (pin "4") (pinfunction "DGND_4") (pintype "passive"))
      (node (ref "IC18") (pin "5") (pinfunction "AVSS_5") (pintype "passive"))
      (node (ref "IC18") (pin "8") (pinfunction "REFN0_8") (pintype "input"))
      (node (ref "IC2") (pin "9") (pinfunction "GND_9") (pintype "passive"))
      (node (ref "IC2") (pin "TP") (pinfunction "TP_TP") (pintype "passive"))
      (node (ref "IC20") (pin "4") (pinfunction "GND_4") (pintype "passive"))
      (node (ref "IC21") (pin "2") (pinfunction "GND_2") (pintype "passive"))
      (node (ref "IC3") (pin "15") (pinfunction "GND2_15") (pintype "passive"))
      (node (ref "IC3") (pin "9") (pinfunction "GND2_2_9") (pintype "passive"))
      (node (ref "IC4") (pin "4") (pinfunction "GND_4") (pintype "passive"))
      (node (ref "IC5") (pin "2") (pinfunction "GND_2") (pintype "passive"))
      (node (ref "IC5") (pin "3") (pinfunction "GND_3") (pintype "passive"))
      (node (ref "IC5") (pin "6") (pinfunction "GND_6") (pintype "passive"))
      (node (ref "IC5") (pin "7") (pinfunction "GND_7") (pintype "passive"))
      (node (ref "IC6") (pin "5") (pinfunction "GND_5") (pintype "passive"))
      (node (ref "IC7") (pin "15") (pinfunction "GND2_15") (pintype "passive"))
      (node (ref "IC7") (pin "9") (pinfunction "GND2_2_9") (pintype "passive"))
      (node (ref "KK3") (pin "1") (pinfunction "1_1") (pintype "passive"))
      (node (ref "KK3") (pin "2") (pinfunction "2_2") (pintype "passive"))
      (node (ref "Q15") (pin "2") (pinfunction "S_2") (pintype "passive"))
      (node (ref "Q16") (pin "2") (pinfunction "S_2") (pintype "passive"))
      (node (ref "Q17") (pin "2") (pinfunction "S_2") (pintype "passive"))
      (node (ref "Q21") (pin "E") (pinfunction "E_E") (pintype "passive"))
      (node (ref "Q23") (pin "2") (pinfunction "S_2") (pintype "passive"))
      (node (ref "Q27") (pin "2") (pinfunction "S_2") (pintype "passive"))
      (node (ref "Q9") (pin "2") (pinfunction "S_2") (pintype "passive"))
      (node (ref "R111") (pin "1") (pinfunction "1_1") (pintype "passive"))
      (node (ref "R114") (pin "1") (pinfunction "1_1") (pintype "passive"))
      (node (ref "R15") (pin "1") (pinfunction "1_1") (pintype "passive"))
      (node (ref "R16") (pin "1") (pinfunction "1_1") (pintype "passive"))
      (node (ref "R19") (pin "1") (pinfunction "1_1") (pintype "passive"))
      (node (ref "R21") (pin "1") (pinfunction "1_1") (pintype "passive"))
      (node (ref "R37") (pin "2") (pinfunction "2_2") (pintype "passive"))
      (node (ref "R55") (pin "1") (pinfunction "1_1") (pintype "passive"))
      (node (ref "R60") (pin "1") (pinfunction "1_1") (pintype "passive"))
      (node (ref "R65") (pin "1") (pinfunction "1_1") (pintype "passive"))
      (node (ref "R73") (pin "2") (pinfunction "2_2") (pintype "passive"))
      (node (ref "R79") (pin "1") (pinfunction "1_1") (pintype "passive"))
      (node (ref "R87") (pin "1") (pinfunction "1_1") (pintype "passive"))
      (node (ref "R89") (pin "2") (pinfunction "2_2") (pintype "passive"))
      (node (ref "R96") (pin "1") (pinfunction "1_1") (pintype "passive"))
      (node (ref "R97") (pin "1") (pinfunction "1_1") (pintype "passive"))
      (node (ref "SH1") (pin "2") (pinfunction "GND_B_2") (pintype "bidirectional"))
      (node (ref "TR1") (pin "4") (pinfunction "4_4") (pintype "passive"))
      (node (ref "X3") (pin "2") (pinfunction "1_2") (pintype "passive"))
      (node (ref "ZD3") (pin "1") (pinfunction "A_1") (pintype "passive"))
      (node (ref "ZD3") (pin "2") (pinfunction "A_2") (pintype "passive"))
    )
    (net (code "34") (name "GNDIO") (class "Default")
      (node (ref "C30") (pin "2") (pinfunction "2_2") (pintype "passive"))
      (node (ref "C35") (pin "2") (pinfunction "2_2") (pintype "passive"))
      (node (ref "C38") (pin "1") (pinfunction "1_1") (pintype "passive"))
      (node (ref "IC3") (pin "2") (pinfunction "GND1_2_2") (pintype "passive"))
      (node (ref "IC3") (pin "8") (pinfunction "GND1_8") (pintype "passive"))
      (node (ref "IC7") (pin "2") (pinfunction "GND1_2_2") (pintype "passive"))
      (node (ref "IC7") (pin "8") (pinfunction "GND1_8") (pintype "passive"))
      (node (ref "IC8") (pin "4") (pinfunction "GND_4") (pintype "passive"))
      (node (ref "IC8") (pin "7") (pinfunction "WP_7") (pintype "input"))
      (node (ref "X2") (pin "11") (pinfunction "1_11") (pintype "passive"))
      (node (ref "X2") (pin "16") (pinfunction "1_16") (pintype "passive"))
      (node (ref "X2") (pin "20") (pinfunction "1_20") (pintype "passive"))
      (node (ref "X2") (pin "25") (pinfunction "1_25") (pintype "passive"))
      (node (ref "X2") (pin "7") (pinfunction "1_7") (pintype "passive"))
    )
    (net (code "35") (name "IRQ") (class "Default")
      (node (ref "IC13") (pin "20") (pinfunction "INTA_20") (pintype "output"))
      (node (ref "IC7") (pin "11") (pinfunction "B4_11") (pintype "input"))
    )
    (net (code "36") (name "ISENSE+") (class "Default")
      (node (ref "IC11") (pin "3") (pinfunction "+IN_3") (pintype "input"))
      (node (ref "R58") (pin "2") (pinfunction "2_2") (pintype "passive"))
      (node (ref "R59") (pin "2") (pinfunction "2_2") (pintype "passive"))
    )
    (net (code "37") (name "ISENSE-") (class "Default")
      (node (ref "IC11") (pin "2") (pinfunction "-IN_2") (pintype "input"))
      (node (ref "R64") (pin "1") (pinfunction "1_1") (pintype "passive"))
      (node (ref "R68") (pin "2") (pinfunction "2_2") (pintype "passive"))
    )
    (net (code "38") (name "I_MON") (class "Default")
      (node (ref "D17") (pin "C") (pinfunction "C_C") (pintype "passive"))
      (node (ref "IC21") (pin "4") (pinfunction "COM_4") (pintype "bidirectional"))
      (node (ref "R115") (pin "1") (pinfunction "1_1") (pintype "passive"))
      (node (ref "R62") (pin "1") (pinfunction "1_1") (pintype "passive"))
      (node (ref "R64") (pin "2") (pinfunction "2_2") (pintype "passive"))
      (node (ref "R81") (pin "1") (pinfunction "1_1") (pintype "passive"))
    )
    (net (code "39") (name "I_SERVO") (class "Default")
      (node (ref "C55") (pin "2") (pinfunction "2_2") (pintype "passive"))
      (node (ref "C60") (pin "2") (pinfunction "2_2") (pintype "passive"))
      (node (ref "D13") (pin "C") (pinfunction "C_C") (pintype "passive"))
      (node (ref "IC10") (pin "1") (pinfunction "OUT_1") (pintype "output"))
      (node (ref "R99") (pin "1") (pinfunction "1_1") (pintype "passive"))
    )
    (net (code "40") (name "I_SET") (class "Default")
      (node (ref "I_SET") (pin "2") (pinfunction "2_2") (pintype "passive"))
      (node (ref "R57") (pin "1") (pinfunction "1_1") (pintype "passive"))
      (node (ref "R77") (pin "1") (pinfunction "1_1") (pintype "passive"))
    )
    (net (code "41") (name "LOOP_CTRL") (class "Default")
      (node (ref "D12") (pin "A") (pinfunction "A_A") (pintype "passive"))
      (node (ref "D13") (pin "A") (pinfunction "A_A") (pintype "passive"))
      (node (ref "R40") (pin "1") (pinfunction "1_1") (pintype "passive"))
      (node (ref "R43") (pin "1") (pinfunction "1_1") (pintype "passive"))
      (node (ref "R94") (pin "2") (pinfunction "2_2") (pintype "passive"))
    )
    (net (code "42") (name "MISO") (class "Default")
      (node (ref "IC13") (pin "14") (pinfunction "SO_14") (pintype "output"))
      (node (ref "IC15") (pin "4") (pinfunction "SI/O_4") (pintype "bidirectional"))
      (node (ref "IC18") (pin "15") (pinfunction "DOUT/~{DRDY}_15") (pintype "output"))
      (node (ref "RN2") (pin "7") (pinfunction "2_7") (pintype "passive"))
    )
    (net (code "43") (name "MOSI") (class "Default")
      (node (ref "IC13") (pin "13") (pinfunction "SI_13") (pintype "input"))
      (node (ref "IC16") (pin "7") (pinfunction "DIN_7") (pintype "input"))
      (node (ref "IC18") (pin "16") (pinfunction "DIN_16") (pintype "input"))
      (node (ref "RN2") (pin "6") (pinfunction "2_6") (pintype "passive"))
    )
    (net (code "44") (name "Net-(C10-Pad1)") (class "Default")
      (node (ref "C10") (pin "1") (pinfunction "1_1") (pintype "passive"))
      (node (ref "C11") (pin "+") (pinfunction "+_+") (pintype "passive"))
      (node (ref "C15") (pin "1") (pinfunction "1_1") (pintype "passive"))
      (node (ref "C16") (pin "+") (pinfunction "+_+") (pintype "passive"))
      (node (ref "L2") (pin "2") (pinfunction "2_2") (pintype "passive"))
      (node (ref "L3") (pin "1") (pinfunction "1_1") (pintype "passive"))
      (node (ref "R4") (pin "1") (pinfunction "1_1") (pintype "passive"))
      (node (ref "R6") (pin "1") (pinfunction "1_1") (pintype "passive"))
      (node (ref "R7") (pin "1") (pinfunction "1_1") (pintype "passive"))
      (node (ref "R9") (pin "1") (pinfunction "1_1") (pintype "passive"))
    )
    (net (code "45") (name "Net-(C12-Pad2)") (class "Default")
      (node (ref "C12") (pin "2") (pinfunction "2_2") (pintype "passive"))
      (node (ref "R5") (pin "2") (pinfunction "2_2") (pintype "passive"))
    )
    (net (code "46") (name "Net-(C18-Pad1)") (class "Default")
      (node (ref "C18") (pin "1") (pinfunction "1_1") (pintype "passive"))
      (node (ref "R8") (pin "1") (pinfunction "1_1") (pintype "passive"))
    )
    (net (code "47") (name "Net-(C19-Pad2)") (class "Default")
      (node (ref "C19") (pin "2") (pinfunction "2_2") (pintype "passive"))
      (node (ref "D3") (pin "A") (pinfunction "A_A") (pintype "passive"))
      (node (ref "Q2") (pin "B") (pinfunction "B_B") (pintype "passive"))
      (node (ref "R10") (pin "1") (pinfunction "1_1") (pintype "passive"))
      (node (ref "R7") (pin "2") (pinfunction "2_2") (pintype "passive"))
    )
    (net (code "48") (name "Net-(C20-Pad1)") (class "Default")
      (node (ref "C20") (pin "1") (pinfunction "1_1") (pintype "passive"))
      (node (ref "D4") (pin "A") (pinfunction "A_A") (pintype "passive"))
      (node (ref "R12") (pin "2") (pinfunction "2_2") (pintype "passive"))
    )
    (net (code "49") (name "Net-(C25-Pad2)") (class "Default")
      (node (ref "C25") (pin "2") (pinfunction "2_2") (pintype "passive"))
      (node (ref "R15") (pin "2") (pinfunction "2_2") (pintype "passive"))
    )
    (net (code "50") (name "Net-(C26-Pad1)") (class "Default")
      (node (ref "C26") (pin "1") (pinfunction "1_1") (pintype "passive"))
      (node (ref "R14") (pin "2") (pinfunction "2_2") (pintype "passive"))
      (node (ref "R18") (pin "2") (pinfunction "2_2") (pintype "passive"))
      (node (ref "TR1") (pin "3") (pinfunction "3_3") (pintype "passive"))
    )
    (net (code "51") (name "Net-(C33-Pad2)") (class "Default")
      (node (ref "C33") (pin "2") (pinfunction "2_2") (pintype "passive"))
      (node (ref "R20") (pin "1") (pinfunction "1_1") (pintype "passive"))
    )
    (net (code "52") (name "Net-(C40-Pad1)") (class "Default")
      (node (ref "C40") (pin "1") (pinfunction "1_1") (pintype "passive"))
      (node (ref "D10") (pin "A") (pinfunction "A_A") (pintype "passive"))
      (node (ref "Q7") (pin "B") (pinfunction "B_B") (pintype "passive"))
      (node (ref "R42") (pin "2") (pinfunction "2_2") (pintype "passive"))
    )
    (net (code "53") (name "Net-(C40-Pad2)") (class "Default")
      (node (ref "C40") (pin "2") (pinfunction "2_2") (pintype "passive"))
      (node (ref "Q7") (pin "C") (pinfunction "C_C") (pintype "passive"))
      (node (ref "R36") (pin "2") (pinfunction "2_2") (pintype "passive"))
    )
    (net (code "54") (name "Net-(C41-Pad2)") (class "Default")
      (node (ref "C41") (pin "2") (pinfunction "2_2") (pintype "passive"))
      (node (ref "R44") (pin "1") (pinfunction "1_1") (pintype "passive"))
    )
    (net (code "55") (name "Net-(C42-Pad1)") (class "Default")
      (node (ref "C42") (pin "1") (pinfunction "1_1") (pintype "passive"))
      (node (ref "R118") (pin "2") (pinfunction "2_2") (pintype "passive"))
      (node (ref "R47") (pin "1") (pinfunction "1_1") (pintype "passive"))
      (node (ref "R48") (pin "2") (pinfunction "2_2") (pintype "passive"))
    )
    (net (code "56") (name "Net-(C44-Pad1)") (class "Default")
      (node (ref "C44") (pin "1") (pinfunction "1_1") (pintype "passive"))
      (node (ref "R51") (pin "2") (pinfunction "2_2") (pintype "passive"))
    )
    (net (code "57") (name "Net-(C47-Pad2)") (class "Default")
      (node (ref "C47") (pin "2") (pinfunction "2_2") (pintype "passive"))
      (node (ref "R53") (pin "1") (pinfunction "1_1") (pintype "passive"))
    )
    (net (code "58") (name "Net-(C48-Pad1)") (class "Default")
      (node (ref "C48") (pin "1") (pinfunction "1_1") (pintype "passive"))
      (node (ref "R56") (pin "1") (pinfunction "1_1") (pintype "passive"))
      (node (ref "R57") (pin "2") (pinfunction "2_2") (pintype "passive"))
    )
    (net (code "59") (name "Net-(C55-Pad1)") (class "Default")
      (node (ref "C55") (pin "1") (pinfunction "1_1") (pintype "passive"))
      (node (ref "R63") (pin "1") (pinfunction "1_1") (pintype "passive"))
    )
    (net (code "60") (name "Net-(C61-Pad2)") (class "Default")
      (node (ref "C61") (pin "2") (pinfunction "2_2") (pintype "passive"))
      (node (ref "R66") (pin "1") (pinfunction "1_1") (pintype "passive"))
    )
    (net (code "61") (name "Net-(C90-Pad2)") (class "Default")
      (node (ref "C90") (pin "2") (pinfunction "2_2") (pintype "passive"))
      (node (ref "Q20") (pin "B") (pinfunction "B_B") (pintype "passive"))
      (node (ref "R104") (pin "1") (pinfunction "1_1") (pintype "passive"))
      (node (ref "R105") (pin "2") (pinfunction "2_2") (pintype "passive"))
      (node (ref "R106") (pin "2") (pinfunction "2_2") (pintype "passive"))
    )
    (net (code "62") (name "Net-(C91-Pad2)") (class "Default")
      (node (ref "C91") (pin "2") (pinfunction "2_2") (pintype "passive"))
      (node (ref "R109") (pin "2") (pinfunction "2_2") (pintype "passive"))
    )
    (net (code "63") (name "Net-(C98-Pad1)") (class "Default")
      (node (ref "C98") (pin "1") (pinfunction "1_1") (pintype "passive"))
      (node (ref "Q22") (pin "B") (pinfunction "B_B") (pintype "passive"))
      (node (ref "R110") (pin "1") (pinfunction "1_1") (pintype "passive"))
      (node (ref "R112") (pin "2") (pinfunction "2_2") (pintype "passive"))
    )
    (net (code "64") (name "Net-(D2-C)") (class "Default")
      (node (ref "C12") (pin "1") (pinfunction "1_1") (pintype "passive"))
      (node (ref "D2") (pin "3") (pinfunction "C_3") (pintype "passive"))
      (node (ref "L2") (pin "1") (pinfunction "1_1") (pintype "passive"))
      (node (ref "Q1") (pin "2") (pinfunction "D_2") (pintype "passive"))
    )
    (net (code "65") (name "Net-(D3-PadC)") (class "Default")
      (node (ref "D3") (pin "C") (pinfunction "C_C") (pintype "passive"))
      (node (ref "Q2") (pin "E") (pinfunction "E_E") (pintype "passive"))
      (node (ref "R6") (pin "2") (pinfunction "2_2") (pintype "passive"))
    )
    (net (code "66") (name "Net-(D4-PadC)") (class "Default")
      (node (ref "D4") (pin "C") (pinfunction "C_C") (pintype "passive"))
      (node (ref "TR1") (pin "2") (pinfunction "2_2") (pintype "passive"))
    )
    (net (code "67") (name "Net-(D18-PadA)") (class "Default")
      (node (ref "D18") (pin "A") (pinfunction "A_A") (pintype "passive"))
      (node (ref "Q14") (pin "B") (pinfunction "B_B") (pintype "passive"))
      (node (ref "R91") (pin "1") (pinfunction "1_1") (pintype "passive"))
      (node (ref "R96") (pin "2") (pinfunction "2_2") (pintype "passive"))
    )
    (net (code "68") (name "Net-(D18-PadC)") (class "Default")
      (node (ref "D18") (pin "C") (pinfunction "C_C") (pintype "passive"))
      (node (ref "D19") (pin "A") (pinfunction "A_A") (pintype "passive"))
    )
    (net (code "69") (name "Net-(FB1-1)") (class "Default")
      (node (ref "C34") (pin "1") (pinfunction "1_1") (pintype "passive"))
      (node (ref "D6") (pin "C") (pinfunction "C_C") (pintype "passive"))
      (node (ref "FB1") (pin "P$1") (pinfunction "1_P$1") (pintype "passive"))
      (node (ref "FB2") (pin "P$1") (pinfunction "1_P$1") (pintype "passive"))
      (node (ref "IC5") (pin "1") (pinfunction "VO_1") (pintype "passive"))
    )
    (net (code "70") (name "Net-(FB3-1)") (class "Default")
      (node (ref "C37") (pin "2") (pinfunction "2_2") (pintype "passive"))
      (node (ref "D7") (pin "A") (pinfunction "A_A") (pintype "passive"))
      (node (ref "FB3") (pin "P$1") (pinfunction "1_P$1") (pintype "passive"))
      (node (ref "IC6") (pin "1") (pinfunction "OUT_1") (pintype "passive"))
    )
    (net (code "71") (name "Net-(IC1-CAP)") (class "Default")
      (node (ref "C8") (pin "1") (pinfunction "1_1") (pintype "passive"))
      (node (ref "IC1") (pin "9") (pinfunction "CAP_9") (pintype "passive"))
    )
    (net (code "72") (name "Net-(IC1-GATE)") (class "Default")
      (node (ref "IC1") (pin "12") (pinfunction "GATE_12") (pintype "output"))
      (node (ref "Q1") (pin "1") (pinfunction "G_1") (pintype "passive"))
    )
    (net (code "73") (name "Net-(IC1-ITH)") (class "Default")
      (node (ref "C17") (pin "1") (pinfunction "1_1") (pintype "passive"))
      (node (ref "IC1") (pin "6") (pinfunction "ITH_6") (pintype "bidirectional"))
      (node (ref "R8") (pin "2") (pinfunction "2_2") (pintype "passive"))
    )
    (net (code "74") (name "Net-(IC1-RUN)") (class "Default")
      (node (ref "D1") (pin "C") (pinfunction "C_C") (pintype "passive"))
      (node (ref "IC1") (pin "8") (pinfunction "RUN_8") (pintype "input"))
      (node (ref "R2") (pin "2") (pinfunction "2_2") (pintype "passive"))
    )
    (net (code "75") (name "Net-(IC1-SENSE)") (class "Default")
      (node (ref "IC1") (pin "10") (pinfunction "SENSE_10") (pintype "input"))
      (node (ref "Q1") (pin "3") (pinfunction "S_3") (pintype "passive"))
      (node (ref "R3") (pin "2") (pinfunction "2_2") (pintype "passive"))
    )
    (net (code "76") (name "Net-(IC1-SS)") (class "Default")
      (node (ref "C9") (pin "2") (pinfunction "2_2") (pintype "passive"))
      (node (ref "IC1") (pin "4") (pinfunction "SS_4") (pintype "input"))
    )
    (net (code "77") (name "Net-(IC2-BOOT)") (class "Default")
      (node (ref "C24") (pin "2") (pinfunction "2_2") (pintype "passive"))
      (node (ref "IC2") (pin "1") (pinfunction "BOOT_1") (pintype "output"))
    )
    (net (code "78") (name "Net-(IC2-COMP)") (class "Default")
      (node (ref "C29") (pin "2") (pinfunction "2_2") (pintype "passive"))
      (node (ref "IC2") (pin "8") (pinfunction "COMP_8") (pintype "output"))
      (node (ref "R20") (pin "2") (pinfunction "2_2") (pintype "passive"))
    )
    (net (code "79") (name "Net-(IC2-EN)") (class "Default")
      (node (ref "IC2") (pin "3") (pinfunction "EN_3") (pintype "input"))
      (node (ref "R13") (pin "1") (pinfunction "1_1") (pintype "passive"))
      (node (ref "R16") (pin "2") (pinfunction "2_2") (pintype "passive"))
    )
    (net (code "80") (name "Net-(IC2-PH)") (class "Default")
      (node (ref "C24") (pin "1") (pinfunction "1_1") (pintype "passive"))
      (node (ref "C25") (pin "1") (pinfunction "1_1") (pintype "passive"))
      (node (ref "D5") (pin "C") (pinfunction "C_C") (pintype "passive"))
      (node (ref "IC2") (pin "10") (pinfunction "PH_10") (pintype "input"))
      (node (ref "TR1") (pin "1") (pinfunction "1_1") (pintype "passive"))
    )
    (net (code "81") (name "Net-(IC2-RT{slash}CLK)") (class "Default")
      (node (ref "IC2") (pin "5") (pinfunction "RT/CLK_5") (pintype "input"))
      (node (ref "R19") (pin "2") (pinfunction "2_2") (pintype "passive"))
    )
    (net (code "82") (name "Net-(IC2-SS{slash}TR)") (class "Default")
      (node (ref "C28") (pin "1") (pinfunction "1_1") (pintype "passive"))
      (node (ref "IC2") (pin "4") (pinfunction "SS/TR_4") (pintype "input"))
    )
    (net (code "83") (name "Net-(IC2-VSENSE)") (class "Default")
      (node (ref "IC2") (pin "7") (pinfunction "VSENSE_7") (pintype "input"))
      (node (ref "R18") (pin "1") (pinfunction "1_1") (pintype "passive"))
      (node (ref "R21") (pin "2") (pinfunction "2_2") (pintype "passive"))
    )
    (net (code "84") (name "Net-(IC3-B1)") (class "Default")
      (node (ref "IC3") (pin "14") (pinfunction "B1_14") (pintype "output"))
      (node (ref "RN2") (pin "1") (pinfunction "1_1") (pintype "passive"))
    )
    (net (code "85") (name "Net-(IC3-B4)") (class "Default")
      (node (ref "IC3") (pin "11") (pinfunction "B4_11") (pintype "input"))
      (node (ref "RN2") (pin "2") (pinfunction "1_2") (pintype "passive"))
    )
    (net (code "86") (name "Net-(IC4-Y0)") (class "Default")
      (node (ref "IC4") (pin "7") (pinfunction "Y0_7") (pintype "output"))
      (node (ref "RN1") (pin "1") (pinfunction "1_1") (pintype "passive"))
    )
    (net (code "87") (name "Net-(IC4-Y1)") (class "Default")
      (node (ref "IC4") (pin "6") (pinfunction "Y1_6") (pintype "output"))
      (node (ref "RN1") (pin "2") (pinfunction "1_2") (pintype "passive"))
    )
    (net (code "88") (name "Net-(IC4-Y2)") (class "Default")
      (node (ref "IC4") (pin "5") (pinfunction "Y2_5") (pintype "output"))
      (node (ref "RN1") (pin "3") (pinfunction "1_3") (pintype "passive"))
    )
    (net (code "89") (name "Net-(IC4-Y3)") (class "Default")
      (node (ref "IC4") (pin "3") (pinfunction "Y3_3") (pintype "output"))
      (node (ref "RN1") (pin "4") (pinfunction "1_4") (pintype "passive"))
    )
    (net (code "90") (name "Net-(IC7-B1)") (class "Default")
      (node (ref "IC7") (pin "14") (pinfunction "B1_14") (pintype "output"))
      (node (ref "RN2") (pin "3") (pinfunction "1_3") (pintype "passive"))
    )
    (net (code "91") (name "Net-(IC7-B2)") (class "Default")
      (node (ref "IC7") (pin "13") (pinfunction "B2_13") (pintype "output"))
      (node (ref "RN2") (pin "4") (pinfunction "1_4") (pintype "passive"))
    )
    (net (code "92") (name "Net-(IC9A-+IN)") (class "Default")
      (node (ref "IC9") (pin "3") (pinfunction "+IN_3") (pintype "input"))
      (node (ref "R44") (pin "2") (pinfunction "2_2") (pintype "passive"))
      (node (ref "R47") (pin "2") (pinfunction "2_2") (pintype "passive"))
    )
    (net (code "93") (name "Net-(IC9A--IN)") (class "Default")
      (node (ref "C46") (pin "1") (pinfunction "1_1") (pintype "passive"))
      (node (ref "IC9") (pin "2") (pinfunction "-IN_2") (pintype "input"))
      (node (ref "R51") (pin "1") (pinfunction "1_1") (pintype "passive"))
      (node (ref "R52") (pin "2") (pinfunction "2_2") (pintype "passive"))
      (node (ref "R53") (pin "2") (pinfunction "2_2") (pintype "passive"))
    )
    (net (code "94") (name "Net-(IC9B-+IN)") (class "Default")
      (node (ref "IC9") (pin "5") (pinfunction "+IN_5") (pintype "input"))
      (node (ref "R41") (pin "2") (pinfunction "2_2") (pintype "passive"))
      (node (ref "R45") (pin "1") (pinfunction "1_1") (pintype "passive"))
    )
    (net (code "95") (name "Net-(IC9B--IN)") (class "Default")
      (node (ref "C43") (pin "1") (pinfunction "1_1") (pintype "passive"))
      (node (ref "IC9") (pin "6") (pinfunction "-IN_6") (pintype "input"))
      (node (ref "R46") (pin "1") (pinfunction "1_1") (pintype "passive"))
      (node (ref "R50") (pin "2") (pinfunction "2_2") (pintype "passive"))
    )
    (net (code "96") (name "Net-(IC10A-+IN)") (class "Default")
      (node (ref "IC10") (pin "3") (pinfunction "+IN_3") (pintype "input"))
      (node (ref "R56") (pin "2") (pinfunction "2_2") (pintype "passive"))
    )
    (net (code "97") (name "Net-(IC10A--IN)") (class "Default")
      (node (ref "C60") (pin "1") (pinfunction "1_1") (pintype "passive"))
      (node (ref "IC10") (pin "2") (pinfunction "-IN_2") (pintype "input"))
      (node (ref "R116") (pin "2") (pinfunction "2_2") (pintype "passive"))
      (node (ref "R62") (pin "2") (pinfunction "2_2") (pintype "passive"))
      (node (ref "R63") (pin "2") (pinfunction "2_2") (pintype "passive"))
      (node (ref "R66") (pin "2") (pinfunction "2_2") (pintype "passive"))
    )
    (net (code "98") (name "Net-(IC10B-+IN)") (class "Default")
      (node (ref "C39") (pin "1") (pinfunction "1_1") (pintype "passive"))
      (node (ref "IC10") (pin "5") (pinfunction "+IN_5") (pintype "input"))
      (node (ref "R31") (pin "2") (pinfunction "2_2") (pintype "passive"))
      (node (ref "R37") (pin "1") (pinfunction "1_1") (pintype "passive"))
    )
    (net (code "99") (name "Net-(IC11A-OUT)") (class "Default")
      (node (ref "IC11") (pin "6") (pinfunction "OUT_6") (pintype "output"))
      (node (ref "R115") (pin "2") (pinfunction "2_2") (pintype "passive"))
    )
    (net (code "100") (name "Net-(IC12A-~{CLR})") (class "Default")
      (node (ref "D15") (pin "A") (pinfunction "A_A") (pintype "passive"))
      (node (ref "D16") (pin "A") (pinfunction "A_A") (pintype "passive"))
      (node (ref "IC12") (pin "6") (pinfunction "~{CLR}_6") (pintype "input"))
      (node (ref "R71") (pin "2") (pinfunction "2_2") (pintype "passive"))
    )
    (net (code "101") (name "Net-(IC13-~{RESET})") (class "Default")
      (node (ref "C63") (pin "1") (pinfunction "1_1") (pintype "passive"))
      (node (ref "IC13") (pin "18") (pinfunction "~{RESET}_18") (pintype "input"))
      (node (ref "JP1") (pin "2") (pinfunction "2_2") (pintype "passive"))
      (node (ref "R69") (pin "2") (pinfunction "2_2") (pintype "passive"))
    )
    (net (code "102") (name "Net-(IC14-TRIM{slash}NR)") (class "Default")
      (node (ref "C71") (pin "1") (pinfunction "1_1") (pintype "passive"))
      (node (ref "IC14") (pin "5") (pinfunction "TRIM/NR_5") (pintype "input"))
    )
    (net (code "103") (name "Net-(IC16-VOUTA)") (class "Default")
      (node (ref "IC16") (pin "4") (pinfunction "VOUTA_4") (pintype "output"))
      (node (ref "I_SET") (pin "1") (pinfunction "1_1") (pintype "passive"))
    )
    (net (code "104") (name "Net-(IC16-VOUTB)") (class "Default")
      (node (ref "IC16") (pin "3") (pinfunction "VOUTB_3") (pintype "output"))
      (node (ref "U_SET") (pin "1") (pinfunction "1_1") (pintype "passive"))
    )
    (net (code "105") (name "Net-(IC17-NO)") (class "Default")
      (node (ref "IC17") (pin "1") (pinfunction "NO_1") (pintype "bidirectional"))
      (node (ref "R75") (pin "1") (pinfunction "1_1") (pintype "passive"))
      (node (ref "ZD3") (pin "3") (pinfunction "C_3") (pintype "passive"))
    )
    (net (code "106") (name "Net-(IC18-AIN0{slash}REFP1)") (class "Default")
      (node (ref "C78") (pin "2") (pinfunction "2_2") (pintype "passive"))
      (node (ref "IC18") (pin "11") (pinfunction "AIN0/REFP1_11") (pintype "input"))
      (node (ref "R80") (pin "2") (pinfunction "2_2") (pintype "passive"))
    )
    (net (code "107") (name "Net-(IC18-AIN1)") (class "Default")
      (node (ref "C75") (pin "2") (pinfunction "2_2") (pintype "passive"))
      (node (ref "IC18") (pin "10") (pinfunction "AIN1_10") (pintype "input"))
      (node (ref "R77") (pin "2") (pinfunction "2_2") (pintype "passive"))
    )
    (net (code "108") (name "Net-(IC18-AIN2)") (class "Default")
      (node (ref "C76") (pin "2") (pinfunction "2_2") (pintype "passive"))
      (node (ref "IC18") (pin "7") (pinfunction "AIN2_7") (pintype "input"))
      (node (ref "R78") (pin "2") (pinfunction "2_2") (pintype "passive"))
    )
    (net (code "109") (name "Net-(IC18-AIN3{slash}REFN1)") (class "Default")
      (node (ref "C77") (pin "1") (pinfunction "1_1") (pintype "passive"))
      (node (ref "IC18") (pin "6") (pinfunction "AIN3/REFN1_6") (pintype "input"))
      (node (ref "R81") (pin "2") (pinfunction "2_2") (pintype "passive"))
    )
    (net (code "110") (name "Net-(IC18-AVDD)") (class "Default")
      (node (ref "C81") (pin "2") (pinfunction "2_2") (pintype "passive"))
      (node (ref "C82") (pin "2") (pinfunction "2_2") (pintype "passive"))
      (node (ref "IC18") (pin "12") (pinfunction "AVDD_12") (pintype "power_in"))
      (node (ref "R82") (pin "2") (pinfunction "2_2") (pintype "passive"))
    )
    (net (code "111") (name "Net-(IC19A-+IN)") (class "Default")
      (node (ref "IC19") (pin "3") (pinfunction "+IN_3") (pintype "input"))
      (node (ref "IC19") (pin "5") (pinfunction "+IN_5") (pintype "input"))
      (node (ref "R94") (pin "1") (pinfunction "1_1") (pintype "passive"))
    )
    (net (code "112") (name "Net-(IC19A--IN)") (class "Default")
      (node (ref "IC19") (pin "2") (pinfunction "-IN_2") (pintype "input"))
      (node (ref "R86") (pin "2") (pinfunction "2_2") (pintype "passive"))
    )
    (net (code "113") (name "Net-(IC19A-OUT)") (class "Default")
      (node (ref "IC19") (pin "1") (pinfunction "OUT_1") (pintype "output"))
      (node (ref "R88") (pin "1") (pinfunction "1_1") (pintype "passive"))
    )
    (net (code "114") (name "Net-(IC19B--IN)") (class "Default")
      (node (ref "IC19") (pin "6") (pinfunction "-IN_6") (pintype "input"))
      (node (ref "R99") (pin "2") (pinfunction "2_2") (pintype "passive"))
    )
    (net (code "115") (name "Net-(IC19B-OUT)") (class "Default")
      (node (ref "IC19") (pin "7") (pinfunction "OUT_7") (pintype "output"))
      (node (ref "R100") (pin "1") (pinfunction "1_1") (pintype "passive"))
    )
    (net (code "116") (name "Net-(IC20-+IN)") (class "Default")
      (node (ref "C86") (pin "2") (pinfunction "2_2") (pintype "passive"))
      (node (ref "C87") (pin "1") (pinfunction "1_1") (pintype "passive"))
      (node (ref "IC20") (pin "2") (pinfunction "+IN_2") (pintype "input"))
      (node (ref "R83") (pin "2") (pinfunction "2_2") (pintype "passive"))
      (node (ref "R89") (pin "1") (pinfunction "1_1") (pintype "passive"))
    )
    (net (code "117") (name "Net-(IC20--IN)") (class "Default")
      (node (ref "C87") (pin "2") (pinfunction "2_2") (pintype "passive"))
      (node (ref "IC20") (pin "3") (pinfunction "-IN_3") (pintype "input"))
      (node (ref "R95") (pin "2") (pinfunction "2_2") (pintype "passive"))
    )
    (net (code "118") (name "Net-(IC20-OUT)") (class "Default")
      (node (ref "IC20") (pin "7") (pinfunction "OUT_7") (pintype "output"))
      (node (ref "Q17") (pin "1") (pinfunction "G_1") (pintype "passive"))
      (node (ref "R101") (pin "2") (pinfunction "2_2") (pintype "passive"))
      (node (ref "R91") (pin "2") (pinfunction "2_2") (pintype "passive"))
    )
    (net (code "119") (name "Net-(IC21-NO)") (class "Default")
      (node (ref "IC21") (pin "1") (pinfunction "NO_1") (pintype "bidirectional"))
      (node (ref "R116") (pin "1") (pinfunction "1_1") (pintype "passive"))
    )
    (net (code "120") (name "Net-(K1A--)") (class "Default")
      (node (ref "D20") (pin "A") (pinfunction "A_A") (pintype "passive"))
      (node (ref "K1") (pin "8") (pinfunction "-_8") (pintype "passive"))
      (node (ref "Q23") (pin "3") (pinfunction "D_3") (pintype "passive"))
      (node (ref "R113") (pin "1") (pinfunction "1_1") (pintype "passive"))
    )
    (net (code "121") (name "Net-(K1B-S)") (class "Default")
      (node (ref "K1") (pin "4") (pinfunction "S_4") (pintype "passive"))
      (node (ref "X3") (pin "4") (pinfunction "1_4") (pintype "passive"))
    )
    (net (code "122") (name "Net-(K1C-S)") (class "Default")
      (node (ref "K1") (pin "5") (pinfunction "S_5") (pintype "passive"))
      (node (ref "X3") (pin "5") (pinfunction "1_5") (pintype "passive"))
    )
    (net (code "123") (name "Net-(LED1-C)") (class "Default")
      (node (ref "LED1") (pin "CC") (pinfunction "C_CC") (pintype "passive"))
      (node (ref "R73") (pin "1") (pinfunction "1_1") (pintype "passive"))
    )
    (net (code "124") (name "Net-(LED2A-C)") (class "Default")
      (node (ref "LED2") (pin "BC") (pinfunction "C_BC") (pintype "passive"))
      (node (ref "R79") (pin "2") (pinfunction "2_2") (pintype "passive"))
    )
    (net (code "125") (name "Net-(LED2B-C)") (class "Default")
      (node (ref "LED2") (pin "TC") (pinfunction "C_TC") (pintype "passive"))
      (node (ref "R113") (pin "2") (pinfunction "2_2") (pintype "passive"))
    )
    (net (code "126") (name "Net-(LED3A-C)") (class "Default")
      (node (ref "LED3") (pin "BC") (pinfunction "C_BC") (pintype "passive"))
      (node (ref "R92") (pin "2") (pinfunction "2_2") (pintype "passive"))
    )
    (net (code "127") (name "Net-(LED3B-C)") (class "Default")
      (node (ref "LED3") (pin "TC") (pinfunction "C_TC") (pintype "passive"))
      (node (ref "R90") (pin "1") (pinfunction "1_1") (pintype "passive"))
    )
    (net (code "128") (name "Net-(Q3-B)") (class "Default")
      (node (ref "Q3") (pin "1") (pinfunction "B_1") (pintype "passive"))
      (node (ref "R34") (pin "2") (pinfunction "2_2") (pintype "passive"))
    )
    (net (code "129") (name "Net-(Q3-E)") (class "Default")
      (node (ref "Q3") (pin "3") (pinfunction "E_3") (pintype "passive"))
      (node (ref "R25") (pin "2") (pinfunction "2_2") (pintype "passive"))
    )
    (net (code "130") (name "Net-(Q4-B)") (class "Default")
      (node (ref "Q4") (pin "1") (pinfunction "B_1") (pintype "passive"))
      (node (ref "R35") (pin "2") (pinfunction "2_2") (pintype "passive"))
    )
    (net (code "131") (name "Net-(Q4-E)") (class "Default")
      (node (ref "Q4") (pin "3") (pinfunction "E_3") (pintype "passive"))
      (node (ref "R26") (pin "2") (pinfunction "2_2") (pintype "passive"))
    )
    (net (code "132") (name "Net-(Q5-G)") (class "Default")
      (node (ref "Q5") (pin "1") (pinfunction "G_1") (pintype "passive"))
      (node (ref "Q6") (pin "2") (pinfunction "C_2") (pintype "passive"))
      (node (ref "Q6") (pin "4") (pinfunction "C_4") (pintype "passive"))
      (node (ref "R30") (pin "2") (pinfunction "2_2") (pintype "passive"))
      (node (ref "ZD2") (pin "A") (pinfunction "A_A") (pintype "passive"))
    )
    (net (code "133") (name "Net-(Q5-S)") (class "Default")
      (node (ref "Q5") (pin "3") (pinfunction "S_3") (pintype "passive"))
      (node (ref "R29") (pin "1") (pinfunction "1_1") (pintype "passive"))
    )
    (net (code "134") (name "Net-(Q6-B)") (class "Default")
      (node (ref "Q6") (pin "1") (pinfunction "B_1") (pintype "passive"))
      (node (ref "R36") (pin "1") (pinfunction "1_1") (pintype "passive"))
      (node (ref "R38") (pin "1") (pinfunction "1_1") (pintype "passive"))
    )
    (net (code "135") (name "Net-(Q6-E)") (class "Default")
      (node (ref "Q6") (pin "3") (pinfunction "E_3") (pintype "passive"))
      (node (ref "R39") (pin "1") (pinfunction "1_1") (pintype "passive"))
    )
    (net (code "136") (name "Net-(Q8-B)") (class "Default")
      (node (ref "D11") (pin "C") (pinfunction "C_C") (pintype "passive"))
      (node (ref "Q8") (pin "1") (pinfunction "B_1") (pintype "passive"))
      (node (ref "R43") (pin "2") (pinfunction "2_2") (pintype "passive"))
    )
    (net (code "137") (name "Net-(Q8-C-Pad2)") (class "Default")
      (node (ref "Q8") (pin "2") (pinfunction "C_2") (pintype "passive"))
      (node (ref "Q8") (pin "4") (pinfunction "C_4") (pintype "passive"))
      (node (ref "R33") (pin "1") (pinfunction "1_1") (pintype "passive"))
      (node (ref "R34") (pin "1") (pinfunction "1_1") (pintype "passive"))
      (node (ref "R35") (pin "1") (pinfunction "1_1") (pintype "passive"))
    )
    (net (code "138") (name "Net-(Q8-E)") (class "Default")
      (node (ref "D11") (pin "A") (pinfunction "A_A") (pintype "passive"))
      (node (ref "Q8") (pin "3") (pinfunction "E_3") (pintype "passive"))
      (node (ref "R49") (pin "2") (pinfunction "2_2") (pintype "passive"))
    )
    (net (code "139") (name "Net-(Q9-D)") (class "Default")
      (node (ref "C45") (pin "2") (pinfunction "2_2") (pintype "passive"))
      (node (ref "Q9") (pin "3") (pinfunction "D_3") (pintype "passive"))
      (node (ref "R49") (pin "1") (pinfunction "1_1") (pintype "passive"))
    )
    (net (code "140") (name "Net-(Q9-G)") (class "Default")
      (node (ref "C45") (pin "1") (pinfunction "1_1") (pintype "passive"))
      (node (ref "Q9") (pin "1") (pinfunction "G_1") (pintype "passive"))
      (node (ref "R54") (pin "1") (pinfunction "1_1") (pintype "passive"))
      (node (ref "R55") (pin "2") (pinfunction "2_2") (pintype "passive"))
    )
    (net (code "141") (name "Net-(Q10-S-Pad1)") (class "Default")
      (node (ref "Q10") (pin "1") (pinfunction "S_1") (pintype "passive"))
      (node (ref "Q10") (pin "2") (pinfunction "S_2") (pintype "passive"))
      (node (ref "Q10") (pin "3") (pinfunction "S_3") (pintype "passive"))
      (node (ref "R59") (pin "1") (pinfunction "1_1") (pintype "passive"))
      (node (ref "R61") (pin "1") (pinfunction "1_1") (pintype "passive"))
    )
    (net (code "142") (name "Net-(Q11-S-Pad1)") (class "Default")
      (node (ref "Q11") (pin "1") (pinfunction "S_1") (pintype "passive"))
      (node (ref "Q11") (pin "2") (pinfunction "S_2") (pintype "passive"))
      (node (ref "Q11") (pin "3") (pinfunction "S_3") (pintype "passive"))
      (node (ref "R67") (pin "2") (pinfunction "2_2") (pintype "passive"))
    )
    (net (code "143") (name "Net-(Q12-D)") (class "Default")
      (node (ref "Q12") (pin "3") (pinfunction "D_3") (pintype "passive"))
      (node (ref "R74") (pin "2") (pinfunction "2_2") (pintype "passive"))
    )
    (net (code "144") (name "Net-(Q13-PadA2)") (class "Default")
      (node (ref "Q13") (pin "A2") (pinfunction "A2_A2") (pintype "passive"))
      (node (ref "R93") (pin "2") (pinfunction "2_2") (pintype "passive"))
    )
    (net (code "145") (name "Net-(Q13-PadG)") (class "Default")
      (node (ref "Q13") (pin "G") (pinfunction "G_G") (pintype "passive"))
      (node (ref "Q14") (pin "C") (pinfunction "C_C") (pintype "passive"))
      (node (ref "R85") (pin "1") (pinfunction "1_1") (pintype "passive"))
    )
    (net (code "146") (name "Net-(Q14-PadE)") (class "Default")
      (node (ref "Q14") (pin "E") (pinfunction "E_E") (pintype "passive"))
      (node (ref "R97") (pin "2") (pinfunction "2_2") (pintype "passive"))
    )
    (net (code "147") (name "Net-(Q15-D)") (class "Default")
      (node (ref "Q15") (pin "3") (pinfunction "D_3") (pintype "passive"))
      (node (ref "R90") (pin "2") (pinfunction "2_2") (pintype "passive"))
    )
    (net (code "148") (name "Net-(Q16-D)") (class "Default")
      (node (ref "Q16") (pin "3") (pinfunction "D_3") (pintype "passive"))
      (node (ref "R92") (pin "1") (pinfunction "1_1") (pintype "passive"))
    )
    (net (code "149") (name "Net-(Q18-G)") (class "Default")
      (node (ref "Q18") (pin "4") (pinfunction "G_4") (pintype "passive"))
      (node (ref "Q19") (pin "C") (pinfunction "C_C") (pintype "passive"))
      (node (ref "R101") (pin "1") (pinfunction "1_1") (pintype "passive"))
    )
    (net (code "150") (name "Net-(Q19-PadB)") (class "Default")
      (node (ref "Q19") (pin "B") (pinfunction "B_B") (pintype "passive"))
      (node (ref "R102") (pin "1") (pinfunction "1_1") (pintype "passive"))
      (node (ref "R103") (pin "2") (pinfunction "2_2") (pintype "passive"))
    )
    (net (code "151") (name "Net-(Q20-PadC)") (class "Default")
      (node (ref "Q20") (pin "C") (pinfunction "C_C") (pintype "passive"))
      (node (ref "R108") (pin "2") (pinfunction "2_2") (pintype "passive"))
    )
    (net (code "152") (name "Net-(Q21-PadB)") (class "Default")
      (node (ref "Q21") (pin "B") (pinfunction "B_B") (pintype "passive"))
      (node (ref "R108") (pin "1") (pinfunction "1_1") (pintype "passive"))
      (node (ref "R111") (pin "2") (pinfunction "2_2") (pintype "passive"))
    )
    (net (code "153") (name "Net-(Q22-PadC)") (class "Default")
      (node (ref "Q22") (pin "C") (pinfunction "C_C") (pintype "passive"))
      (node (ref "R106") (pin "1") (pinfunction "1_1") (pintype "passive"))
    )
    (net (code "154") (name "Net-(Q27-D)") (class "Default")
      (node (ref "Q27") (pin "3") (pinfunction "D_3") (pintype "passive"))
      (node (ref "R118") (pin "1") (pinfunction "1_1") (pintype "passive"))
    )
    (net (code "155") (name "Net-(R27-Pad1)") (class "Default")
      (node (ref "R27") (pin "1") (pinfunction "1_1") (pintype "passive"))
      (node (ref "R32") (pin "2") (pinfunction "2_2") (pintype "passive"))
    )
    (net (code "156") (name "Net-(R61-Pad2)") (class "Default")
      (node (ref "R61") (pin "2") (pinfunction "2_2") (pintype "passive"))
      (node (ref "R67") (pin "2S") (pinfunction "2S_2S") (pintype "passive"))
    )
    (net (code "157") (name "Net-(R67-Pad1S)") (class "Default")
      (node (ref "R67") (pin "1S") (pinfunction "1S_1S") (pintype "passive"))
      (node (ref "R68") (pin "1") (pinfunction "1_1") (pintype "passive"))
    )
    (net (code "158") (name "Net-(R75-Pad2)") (class "Default")
      (node (ref "R75") (pin "2") (pinfunction "2_2") (pintype "passive"))
      (node (ref "R76") (pin "1") (pinfunction "1_1") (pintype "passive"))
    )
    (net (code "159") (name "Net-(R76-Pad2)") (class "Default")
      (node (ref "R76") (pin "2") (pinfunction "2_2") (pintype "passive"))
      (node (ref "X3") (pin "1") (pinfunction "1_1") (pintype "passive"))
    )
    (net (code "160") (name "Net-(R102-Pad2)") (class "Default")
      (node (ref "R102") (pin "2") (pinfunction "2_2") (pintype "passive"))
      (node (ref "ZD4") (pin "A") (pinfunction "A_A") (pintype "passive"))
    )
    (net (code "161") (name "Net-(X4B-1)") (class "Default")
      (node (ref "F2") (pin "2") (pinfunction "2_2") (pintype "passive"))
      (node (ref "X4") (pin "10") (pinfunction "1_10") (pintype "passive"))
      (node (ref "X4") (pin "6") (pinfunction "1_6") (pintype "passive"))
      (node (ref "X4") (pin "7") (pinfunction "1_7") (pintype "passive"))
      (node (ref "X4") (pin "8") (pinfunction "1_8") (pintype "passive"))
      (node (ref "X4") (pin "9") (pinfunction "1_9") (pintype "passive"))
    )
    (net (code "162") (name "OE") (class "Default")
      (node (ref "IC13") (pin "2") (pinfunction "GPB1_2") (pintype "bidirectional"))
      (node (ref "OE") (pin "1") (pinfunction "1_1") (pintype "passive"))
    )
    (net (code "163") (name "OE_GREEN") (class "Default")
      (node (ref "IC13") (pin "7") (pinfunction "GPB6_7") (pintype "bidirectional"))
      (node (ref "LED1") (pin "GREEN") (pinfunction "AG_GREEN") (pintype "passive"))
    )
    (net (code "164") (name "OE_RED") (class "Default")
      (node (ref "IC13") (pin "8") (pinfunction "GPB7_8") (pintype "bidirectional"))
      (node (ref "LED1") (pin "RED") (pinfunction "AR_RED") (pintype "passive"))
    )
    (net (code "165") (name "OE_SYNC") (class "Default")
      (node (ref "IC7") (pin "4") (pinfunction "A2_4") (pintype "input"))
      (node (ref "X2") (pin "6") (pinfunction "1_6") (pintype "passive"))
    )
    (net (code "166") (name "OE_TRIG") (class "Default")
      (node (ref "IC12") (pin "1") (pinfunction "CLK_1") (pintype "input"))
      (node (ref "RN2") (pin "5") (pinfunction "2_5") (pintype "passive"))
    )
    (net (code "167") (name "OUTC+") (class "Default")
      (node (ref "C93") (pin "1") (pinfunction "1_1") (pintype "passive"))
      (node (ref "C94") (pin "+") (pinfunction "+_+") (pintype "passive"))
      (node (ref "C95") (pin "1") (pinfunction "1_1") (pintype "passive"))
      (node (ref "C96") (pin "1") (pinfunction "1_1") (pintype "passive"))
      (node (ref "J2") (pin "1") (pinfunction "1_1") (pintype "passive"))
      (node (ref "J2") (pin "NC1") (pinfunction "1_NC1") (pintype "passive"))
      (node (ref "J2") (pin "NC2") (pinfunction "1_NC2") (pintype "passive"))
      (node (ref "J2") (pin "NC3") (pinfunction "1_NC3") (pintype "passive"))
      (node (ref "J2") (pin "NC4") (pinfunction "1_NC4") (pintype "passive"))
      (node (ref "X4") (pin "1") (pinfunction "1_1") (pintype "passive"))
      (node (ref "X4") (pin "2") (pinfunction "1_2") (pintype "passive"))
      (node (ref "X4") (pin "3") (pinfunction "1_3") (pintype "passive"))
      (node (ref "X4") (pin "4") (pinfunction "1_4") (pintype "passive"))
      (node (ref "X4") (pin "5") (pinfunction "1_5") (pintype "passive"))
    )
    (net (code "168") (name "OUTC-") (class "Default")
      (node (ref "C94") (pin "-") (pinfunction "-_-") (pintype "passive"))
      (node (ref "C95") (pin "2") (pinfunction "2_2") (pintype "passive"))
      (node (ref "C96") (pin "2") (pinfunction "2_2") (pintype "passive"))
      (node (ref "C97") (pin "2") (pinfunction "2_2") (pintype "passive"))
      (node (ref "J3") (pin "1") (pinfunction "1_1") (pintype "passive"))
      (node (ref "J3") (pin "NC1") (pinfunction "1_NC1") (pintype "passive"))
      (node (ref "J3") (pin "NC2") (pinfunction "1_NC2") (pintype "passive"))
      (node (ref "J3") (pin "NC3") (pinfunction "1_NC3") (pintype "passive"))
      (node (ref "J3") (pin "NC4") (pinfunction "1_NC4") (pintype "passive"))
      (node (ref "X4") (pin "16") (pinfunction "1_16") (pintype "passive"))
      (node (ref "X4") (pin "17") (pinfunction "1_17") (pintype "passive"))
      (node (ref "X4") (pin "18") (pinfunction "1_18") (pintype "passive"))
      (node (ref "X4") (pin "19") (pinfunction "1_19") (pintype "passive"))
      (node (ref "X4") (pin "20") (pinfunction "1_20") (pintype "passive"))
    )
    (net (code "169") (name "OVP_EN") (class "Default")
      (node (ref "IC13") (pin "5") (pinfunction "GPB4_5") (pintype "bidirectional"))
      (node (ref "IC20") (pin "6") (pinfunction "~{SHDN}_6") (pintype "input"))
      (node (ref "R87") (pin "2") (pinfunction "2_2") (pintype "passive"))
    )
    (net (code "170") (name "PE") (class "Default")
      (node (ref "C3") (pin "2") (pinfunction "2_2") (pintype "passive"))
      (node (ref "C4") (pin "1") (pinfunction "1_1") (pintype "passive"))
      (node (ref "C93") (pin "2") (pinfunction "2_2") (pintype "passive"))
      (node (ref "C97") (pin "1") (pinfunction "1_1") (pintype "passive"))
      (node (ref "J1") (pin "1") (pinfunction "P$1_1") (pintype "bidirectional"))
      (node (ref "J1") (pin "2") (pinfunction "P$1_2") (pintype "bidirectional"))
      (node (ref "X3") (pin "3") (pinfunction "1_3") (pintype "passive"))
    )
    (net (code "171") (name "POST_OE") (class "Default")
      (node (ref "IC12") (pin "5") (pinfunction "Q_5") (pintype "output"))
      (node (ref "R54") (pin "2") (pinfunction "2_2") (pintype "passive"))
    )
    (net (code "172") (name "POST_OUT+") (class "Default")
      (node (ref "C47") (pin "1") (pinfunction "1_1") (pintype "passive"))
      (node (ref "C61") (pin "1") (pinfunction "1_1") (pintype "passive"))
      (node (ref "D8") (pin "A") (pinfunction "A_A") (pintype "passive"))
      (node (ref "F1") (pin "1") (pinfunction "1_1") (pintype "passive"))
      (node (ref "Q3") (pin "2") (pinfunction "C_2") (pintype "passive"))
      (node (ref "Q4") (pin "2") (pinfunction "C_2") (pintype "passive"))
      (node (ref "R10") (pin "2") (pinfunction "2_2") (pintype "passive"))
      (node (ref "R27") (pin "2") (pinfunction "2_2") (pintype "passive"))
      (node (ref "R28") (pin "2") (pinfunction "2_2") (pintype "passive"))
      (node (ref "R29") (pin "2") (pinfunction "2_2") (pintype "passive"))
      (node (ref "R30") (pin "1") (pinfunction "1_1") (pintype "passive"))
      (node (ref "ZD2") (pin "C") (pinfunction "C_C") (pintype "passive"))
    )
    (net (code "173") (name "POST_OUT-") (class "Default")
      (node (ref "C41") (pin "1") (pinfunction "1_1") (pintype "passive"))
      (node (ref "C92") (pin "-") (pinfunction "-_-") (pintype "passive"))
      (node (ref "C98") (pin "2") (pinfunction "2_2") (pintype "passive"))
      (node (ref "D14") (pin "A") (pinfunction "A_A") (pintype "passive"))
      (node (ref "JP4") (pin "1") (pinfunction "1_1") (pintype "passive"))
      (node (ref "K1") (pin "7") (pinfunction "O_7") (pintype "passive"))
      (node (ref "Q10") (pin "MB") (pinfunction "D_MB") (pintype "passive"))
      (node (ref "Q11") (pin "MB") (pinfunction "D_MB") (pintype "passive"))
      (node (ref "Q22") (pin "E") (pinfunction "E_E") (pintype "passive"))
      (node (ref "R109") (pin "1") (pinfunction "1_1") (pintype "passive"))
      (node (ref "R112") (pin "1") (pinfunction "1_1") (pintype "passive"))
      (node (ref "X4") (pin "11") (pinfunction "1_11") (pintype "passive"))
      (node (ref "X4") (pin "12") (pinfunction "1_12") (pintype "passive"))
      (node (ref "X4") (pin "13") (pinfunction "1_13") (pintype "passive"))
      (node (ref "X4") (pin "14") (pinfunction "1_14") (pintype "passive"))
      (node (ref "X4") (pin "15") (pinfunction "1_15") (pintype "passive"))
      (node (ref "ZD5") (pin "A") (pinfunction "A_A") (pintype "passive"))
    )
    (net (code "174") (name "POST_OUTF+") (class "Default")
      (node (ref "C90") (pin "1") (pinfunction "1_1") (pintype "passive"))
      (node (ref "C91") (pin "1") (pinfunction "1_1") (pintype "passive"))
      (node (ref "C92") (pin "+") (pinfunction "+_+") (pintype "passive"))
      (node (ref "F1") (pin "2") (pinfunction "2_2") (pintype "passive"))
      (node (ref "F2") (pin "1") (pinfunction "1_1") (pintype "passive"))
      (node (ref "JP3") (pin "2") (pinfunction "2_2") (pintype "passive"))
      (node (ref "K1") (pin "2") (pinfunction "O_2") (pintype "passive"))
      (node (ref "Q13") (pin "A1") (pinfunction "A1_A1") (pintype "passive"))
      (node (ref "Q18") (pin "MB") (pinfunction "D_MB") (pintype "passive"))
      (node (ref "Q20") (pin "E") (pinfunction "E_E") (pintype "passive"))
      (node (ref "R104") (pin "2") (pinfunction "2_2") (pintype "passive"))
      (node (ref "R85") (pin "2") (pinfunction "2_2") (pintype "passive"))
      (node (ref "ZD4") (pin "C") (pinfunction "C_C") (pintype "passive"))
      (node (ref "ZD5") (pin "C") (pinfunction "C_C") (pintype "passive"))
    )
    (net (code "175") (name "PREG_IN-") (class "Default")
      (node (ref "C10") (pin "2") (pinfunction "2_2") (pintype "passive"))
      (node (ref "C11") (pin "-") (pinfunction "-_-") (pintype "passive"))
      (node (ref "C15") (pin "2") (pinfunction "2_2") (pintype "passive"))
      (node (ref "C16") (pin "-") (pinfunction "-_-") (pintype "passive"))
      (node (ref "C2") (pin "-") (pinfunction "-_-") (pintype "passive"))
      (node (ref "C3") (pin "1") (pinfunction "1_1") (pintype "passive"))
      (node (ref "C5") (pin "2") (pinfunction "2_2") (pintype "passive"))
      (node (ref "C6") (pin "2") (pinfunction "2_2") (pintype "passive"))
      (node (ref "C7") (pin "2") (pinfunction "2_2") (pintype "passive"))
      (node (ref "D2") (pin "1") (pinfunction "A_1") (pintype "passive"))
      (node (ref "D2") (pin "2") (pinfunction "A_2") (pintype "passive"))
      (node (ref "IC1") (pin "TP") (pinfunction "PGND_TP") (pintype "passive"))
      (node (ref "L1") (pin "4") (pinfunction "2_4") (pintype "passive"))
      (node (ref "R2") (pin "1") (pinfunction "1_1") (pintype "passive"))
      (node (ref "R5") (pin "1") (pinfunction "1_1") (pintype "passive"))
      (node (ref "SH1") (pin "1") (pinfunction "GND_A_1") (pintype "bidirectional"))
      (node (ref "SH2") (pin "2") (pinfunction "GND_B_2") (pintype "bidirectional"))
      (node (ref "SH3") (pin "2") (pinfunction "GND_B_2") (pintype "bidirectional"))
      (node (ref "ZD1") (pin "A") (pinfunction "A_A") (pintype "passive"))
    )
    (net (code "176") (name "PREG_OUT+") (class "Default")
      (node (ref "C13") (pin "+") (pinfunction "+_+") (pintype "passive"))
      (node (ref "C14") (pin "1") (pinfunction "1_1") (pintype "passive"))
      (node (ref "D8") (pin "C") (pinfunction "C_C") (pintype "passive"))
      (node (ref "L3") (pin "2") (pinfunction "2_2") (pintype "passive"))
      (node (ref "R25") (pin "1") (pinfunction "1_1") (pintype "passive"))
      (node (ref "R26") (pin "1") (pinfunction "1_1") (pintype "passive"))
      (node (ref "R33") (pin "2") (pinfunction "2_2") (pintype "passive"))
      (node (ref "R4") (pin "2") (pinfunction "2_2") (pintype "passive"))
    )
    (net (code "177") (name "PREG_OUT-") (class "Default")
      (node (ref "C13") (pin "-") (pinfunction "-_-") (pintype "passive"))
      (node (ref "C14") (pin "2") (pinfunction "2_2") (pintype "passive"))
      (node (ref "D14") (pin "C") (pinfunction "C_C") (pintype "passive"))
      (node (ref "Q18") (pin "1") (pinfunction "S_1") (pintype "passive"))
      (node (ref "Q18") (pin "2") (pinfunction "S_2") (pintype "passive"))
      (node (ref "Q18") (pin "3") (pinfunction "S_3") (pintype "passive"))
      (node (ref "Q19") (pin "E") (pinfunction "E_E") (pintype "passive"))
      (node (ref "Q5") (pin "2") (pinfunction "D_2") (pintype "passive"))
      (node (ref "R103") (pin "1") (pinfunction "1_1") (pintype "passive"))
      (node (ref "R32") (pin "1") (pinfunction "1_1") (pintype "passive"))
      (node (ref "R67") (pin "1") (pinfunction "1_1") (pintype "passive"))
      (node (ref "R93") (pin "1") (pinfunction "1_1") (pintype "passive"))
      (node (ref "SH2") (pin "1") (pinfunction "GND_A_1") (pintype "bidirectional"))
    )
    (net (code "178") (name "PRE_OE") (class "Default")
      (node (ref "D1") (pin "A") (pinfunction "A_A") (pintype "passive"))
      (node (ref "IC12") (pin "2") (pinfunction "D_2") (pintype "input"))
      (node (ref "OE") (pin "2") (pinfunction "2_2") (pintype "passive"))
    )
    (net (code "179") (name "PWRGOOD") (class "Default")
      (node (ref "D16") (pin "C") (pinfunction "C_C") (pintype "passive"))
      (node (ref "IC13") (pin "24") (pinfunction "GPA3_24") (pintype "bidirectional"))
      (node (ref "IC2") (pin "6") (pinfunction "PWRGD_6") (pintype "output"))
      (node (ref "R17") (pin "2") (pinfunction "2_2") (pintype "passive"))
    )
    (net (code "180") (name "RSENSE") (class "Default")
      (node (ref "IC13") (pin "3") (pinfunction "GPB2_3") (pintype "bidirectional"))
      (node (ref "Q23") (pin "1") (pinfunction "G_1") (pintype "passive"))
      (node (ref "R114") (pin "2") (pinfunction "2_2") (pintype "passive"))
    )
    (net (code "181") (name "SCLK") (class "Default")
      (node (ref "IC13") (pin "12") (pinfunction "SCK_12") (pintype "input"))
      (node (ref "IC15") (pin "3") (pinfunction "SCLK_3") (pintype "input"))
      (node (ref "IC16") (pin "6") (pinfunction "SCLK_6") (pintype "input"))
      (node (ref "IC18") (pin "1") (pinfunction "SCLK_1") (pintype "input"))
      (node (ref "RN2") (pin "8") (pinfunction "2_8") (pintype "passive"))
    )
    (net (code "182") (name "SENSE+") (class "Default")
      (node (ref "JP3") (pin "1") (pinfunction "1_1") (pintype "passive"))
      (node (ref "K1") (pin "3") (pinfunction "P_3") (pintype "passive"))
      (node (ref "R105") (pin "1") (pinfunction "1_1") (pintype "passive"))
      (node (ref "R45") (pin "2") (pinfunction "2_2") (pintype "passive"))
    )
    (net (code "183") (name "SENSE-") (class "Default")
      (node (ref "JP4") (pin "2") (pinfunction "2_2") (pintype "passive"))
      (node (ref "K1") (pin "6") (pinfunction "P_6") (pintype "passive"))
      (node (ref "R110") (pin "2") (pinfunction "2_2") (pintype "passive"))
      (node (ref "R46") (pin "2") (pinfunction "2_2") (pintype "passive"))
    )
    (net (code "184") (name "SENSE_ERR") (class "Default")
      (node (ref "IC13") (pin "21") (pinfunction "GPA0_21") (pintype "bidirectional"))
      (node (ref "Q21") (pin "C") (pinfunction "C_C") (pintype "passive"))
      (node (ref "R107") (pin "1") (pinfunction "1_1") (pintype "passive"))
    )
    (net (code "185") (name "SGND") (class "Default")
      (node (ref "C17") (pin "2") (pinfunction "2_2") (pintype "passive"))
      (node (ref "C18") (pin "2") (pinfunction "2_2") (pintype "passive"))
      (node (ref "C9") (pin "1") (pinfunction "1_1") (pintype "passive"))
      (node (ref "IC1") (pin "1") (pinfunction "PLLIN/MODE_1") (pintype "input"))
      (node (ref "IC1") (pin "2") (pinfunction "FREQ_2") (pintype "input"))
      (node (ref "IC1") (pin "3") (pinfunction "SGND_3") (pintype "passive"))
      (node (ref "R11") (pin "2") (pinfunction "2_2") (pintype "passive"))
      (node (ref "SH3") (pin "1") (pinfunction "GND_A_1") (pintype "bidirectional"))
    )
    (net (code "186") (name "TEMP_CS") (class "Default")
      (node (ref "IC15") (pin "1") (pinfunction "~{CS}_1") (pintype "input"))
      (node (ref "RN1") (pin "5") (pinfunction "2_5") (pintype "passive"))
    )
    (net (code "187") (name "U_MON") (class "Default")
      (node (ref "C43") (pin "2") (pinfunction "2_2") (pintype "passive"))
      (node (ref "IC9") (pin "7") (pinfunction "OUT_7") (pintype "output"))
      (node (ref "R50") (pin "1") (pinfunction "1_1") (pintype "passive"))
      (node (ref "R52") (pin "1") (pinfunction "1_1") (pintype "passive"))
      (node (ref "R80") (pin "1") (pinfunction "1_1") (pintype "passive"))
      (node (ref "R83") (pin "1") (pinfunction "1_1") (pintype "passive"))
    )
    (net (code "188") (name "U_SERVO") (class "Default")
      (node (ref "C44") (pin "2") (pinfunction "2_2") (pintype "passive"))
      (node (ref "C46") (pin "2") (pinfunction "2_2") (pintype "passive"))
      (node (ref "D12") (pin "C") (pinfunction "C_C") (pintype "passive"))
      (node (ref "IC9") (pin "1") (pinfunction "OUT_1") (pintype "output"))
      (node (ref "R42") (pin "1") (pinfunction "1_1") (pintype "passive"))
      (node (ref "R86") (pin "1") (pinfunction "1_1") (pintype "passive"))
    )
    (net (code "189") (name "U_SET") (class "Default")
      (node (ref "IC17") (pin "3") (pinfunction "NC_3") (pintype "bidirectional"))
      (node (ref "JP2") (pin "1") (pinfunction "1_1") (pintype "passive"))
      (node (ref "R78") (pin "1") (pinfunction "1_1") (pintype "passive"))
      (node (ref "U_SET") (pin "2") (pinfunction "2_2") (pintype "passive"))
    )
    (net (code "190") (name "U_SET_OUT") (class "Default")
      (node (ref "IC17") (pin "4") (pinfunction "COM_4") (pintype "bidirectional"))
      (node (ref "JP2") (pin "2") (pinfunction "2_2") (pintype "passive"))
      (node (ref "R48") (pin "1") (pinfunction "1_1") (pintype "passive"))
      (node (ref "R95") (pin "1") (pinfunction "1_1") (pintype "passive"))
    )
    (net (code "191") (name "V+") (class "Default")
      (node (ref "C49") (pin "2") (pinfunction "2_2") (pintype "passive"))
      (node (ref "C50") (pin "1") (pinfunction "1_1") (pintype "passive"))
      (node (ref "C51") (pin "2") (pinfunction "2_2") (pintype "passive"))
      (node (ref "C52") (pin "2") (pinfunction "2_2") (pintype "passive"))
      (node (ref "C53") (pin "2") (pinfunction "2_2") (pintype "passive"))
      (node (ref "C62") (pin "1") (pinfunction "1_1") (pintype "passive"))
      (node (ref "C67") (pin "1") (pinfunction "1_1") (pintype "passive"))
      (node (ref "C70") (pin "1") (pinfunction "1_1") (pintype "passive"))
      (node (ref "C72") (pin "2") (pinfunction "2_2") (pintype "passive"))
      (node (ref "C74") (pin "1") (pinfunction "1_1") (pintype "passive"))
      (node (ref "C84") (pin "1") (pinfunction "1_1") (pintype "passive"))
      (node (ref "C85") (pin "2") (pinfunction "2_2") (pintype "passive"))
      (node (ref "C88") (pin "2") (pinfunction "2_2") (pintype "passive"))
      (node (ref "FB1") (pin "P$2") (pinfunction "2_P$2") (pintype "passive"))
      (node (ref "IC10") (pin "8") (pinfunction "V+_8") (pintype "power_in"))
      (node (ref "IC11") (pin "7") (pinfunction "V+_7") (pintype "power_in"))
      (node (ref "IC14") (pin "2") (pinfunction "VIN_2") (pintype "passive"))
      (node (ref "IC16") (pin "1") (pinfunction "VDD_1") (pintype "power_in"))
      (node (ref "IC17") (pin "5") (pinfunction "VDD_5") (pintype "power_in"))
      (node (ref "IC19") (pin "8") (pinfunction "V+_8") (pintype "power_in"))
      (node (ref "IC20") (pin "1") (pinfunction "+VCC_1") (pintype "passive"))
      (node (ref "IC20") (pin "5") (pinfunction "~{LE}_5") (pintype "input"))
      (node (ref "IC21") (pin "5") (pinfunction "VDD_5") (pintype "power_in"))
      (node (ref "IC9") (pin "8") (pinfunction "V+_8") (pintype "power_in"))
      (node (ref "R40") (pin "2") (pinfunction "2_2") (pintype "passive"))
      (node (ref "R82") (pin "1") (pinfunction "1_1") (pintype "passive"))
    )
    (net (code "192") (name "V-") (class "Default")
      (node (ref "C54") (pin "2") (pinfunction "2_2") (pintype "passive"))
      (node (ref "C56") (pin "2") (pinfunction "2_2") (pintype "passive"))
      (node (ref "C57") (pin "1") (pinfunction "1_1") (pintype "passive"))
      (node (ref "C58") (pin "2") (pinfunction "2_2") (pintype "passive"))
      (node (ref "C59") (pin "2") (pinfunction "2_2") (pintype "passive"))
      (node (ref "C89") (pin "2") (pinfunction "2_2") (pintype "passive"))
      (node (ref "FB3") (pin "P$2") (pinfunction "2_P$2") (pintype "passive"))
      (node (ref "IC10") (pin "4") (pinfunction "V-_4") (pintype "power_in"))
      (node (ref "IC11") (pin "4") (pinfunction "V-_4") (pintype "power_in"))
      (node (ref "IC19") (pin "4") (pinfunction "V-_4") (pintype "power_in"))
      (node (ref "IC9") (pin "4") (pinfunction "V-_4") (pintype "power_in"))
    )
    (net (code "193") (name "unconnected-(IC1-PGOOD-Pad7)") (class "Default")
      (node (ref "IC1") (pin "7") (pinfunction "PGOOD_7") (pintype "output"))
    )
    (net (code "194") (name "unconnected-(IC12A-~{Q}-Pad3)") (class "Default")
      (node (ref "IC12") (pin "3") (pinfunction "~{Q}_3") (pintype "output"))
    )
    (net (code "195") (name "unconnected-(IC13-GPB5-Pad6)") (class "Default")
      (node (ref "IC13") (pin "6") (pinfunction "GPB5_6") (pintype "bidirectional"))
    )
    (net (code "196") (name "unconnected-(IC13-INTB-Pad19)") (class "Default")
      (node (ref "IC13") (pin "19") (pinfunction "INTB_19") (pintype "output"))
    )
    (net (code "197") (name "unconnected-(IC14-TEMP-Pad3)") (class "Default")
      (node (ref "IC14") (pin "3") (pinfunction "TEMP_3") (pintype "input"))
    )
    (net (code "198") (name "unconnected-(IC21-NC-Pad3)") (class "Default")
      (node (ref "IC21") (pin "3") (pinfunction "NC_3") (pintype "bidirectional"))
    )
    (net (code "199") (name "~{ADC_DRDY}") (class "Default")
      (node (ref "IC13") (pin "25") (pinfunction "GPA4_25") (pintype "bidirectional"))
      (node (ref "IC18") (pin "14") (pinfunction "~{DRDY}_14") (pintype "output"))
    )
    (net (code "200") (name "~{DP_DRIVE}") (class "Default")
      (node (ref "D9") (pin "A") (pinfunction "A_A") (pintype "passive"))
      (node (ref "Q7") (pin "E") (pinfunction "E_E") (pintype "passive"))
      (node (ref "R74") (pin "1") (pinfunction "1_1") (pintype "passive"))
    )
    (net (code "201") (name "~{OVP_FAULT}") (class "Default")
      (node (ref "C64") (pin "1") (pinfunction "1_1") (pintype "passive"))
      (node (ref "D15") (pin "C") (pinfunction "C_C") (pintype "passive"))
      (node (ref "IC13") (pin "26") (pinfunction "GPA5_26") (pintype "bidirectional"))
      (node (ref "Q17") (pin "3") (pinfunction "D_3") (pintype "passive"))
      (node (ref "R70") (pin "2") (pinfunction "2_2") (pintype "passive"))
    )
    (net (code "202") (name "~{RESET}") (class "Default")
      (node (ref "IC7") (pin "12") (pinfunction "B3_12") (pintype "output"))
      (node (ref "JP1") (pin "1") (pinfunction "1_1") (pintype "passive"))
    )
    (net (code "203") (name "~{SET_DP}") (class "Default")
      (node (ref "IC13") (pin "1") (pinfunction "GPB0_1") (pintype "bidirectional"))
      (node (ref "Q12") (pin "1") (pinfunction "G_1") (pintype "passive"))
      (node (ref "R72") (pin "2") (pinfunction "2_2") (pintype "passive"))
    )
  )
)
